# OSSI-1_COMMS.net
KiCad netlist of a schematic drawn in EAGLE
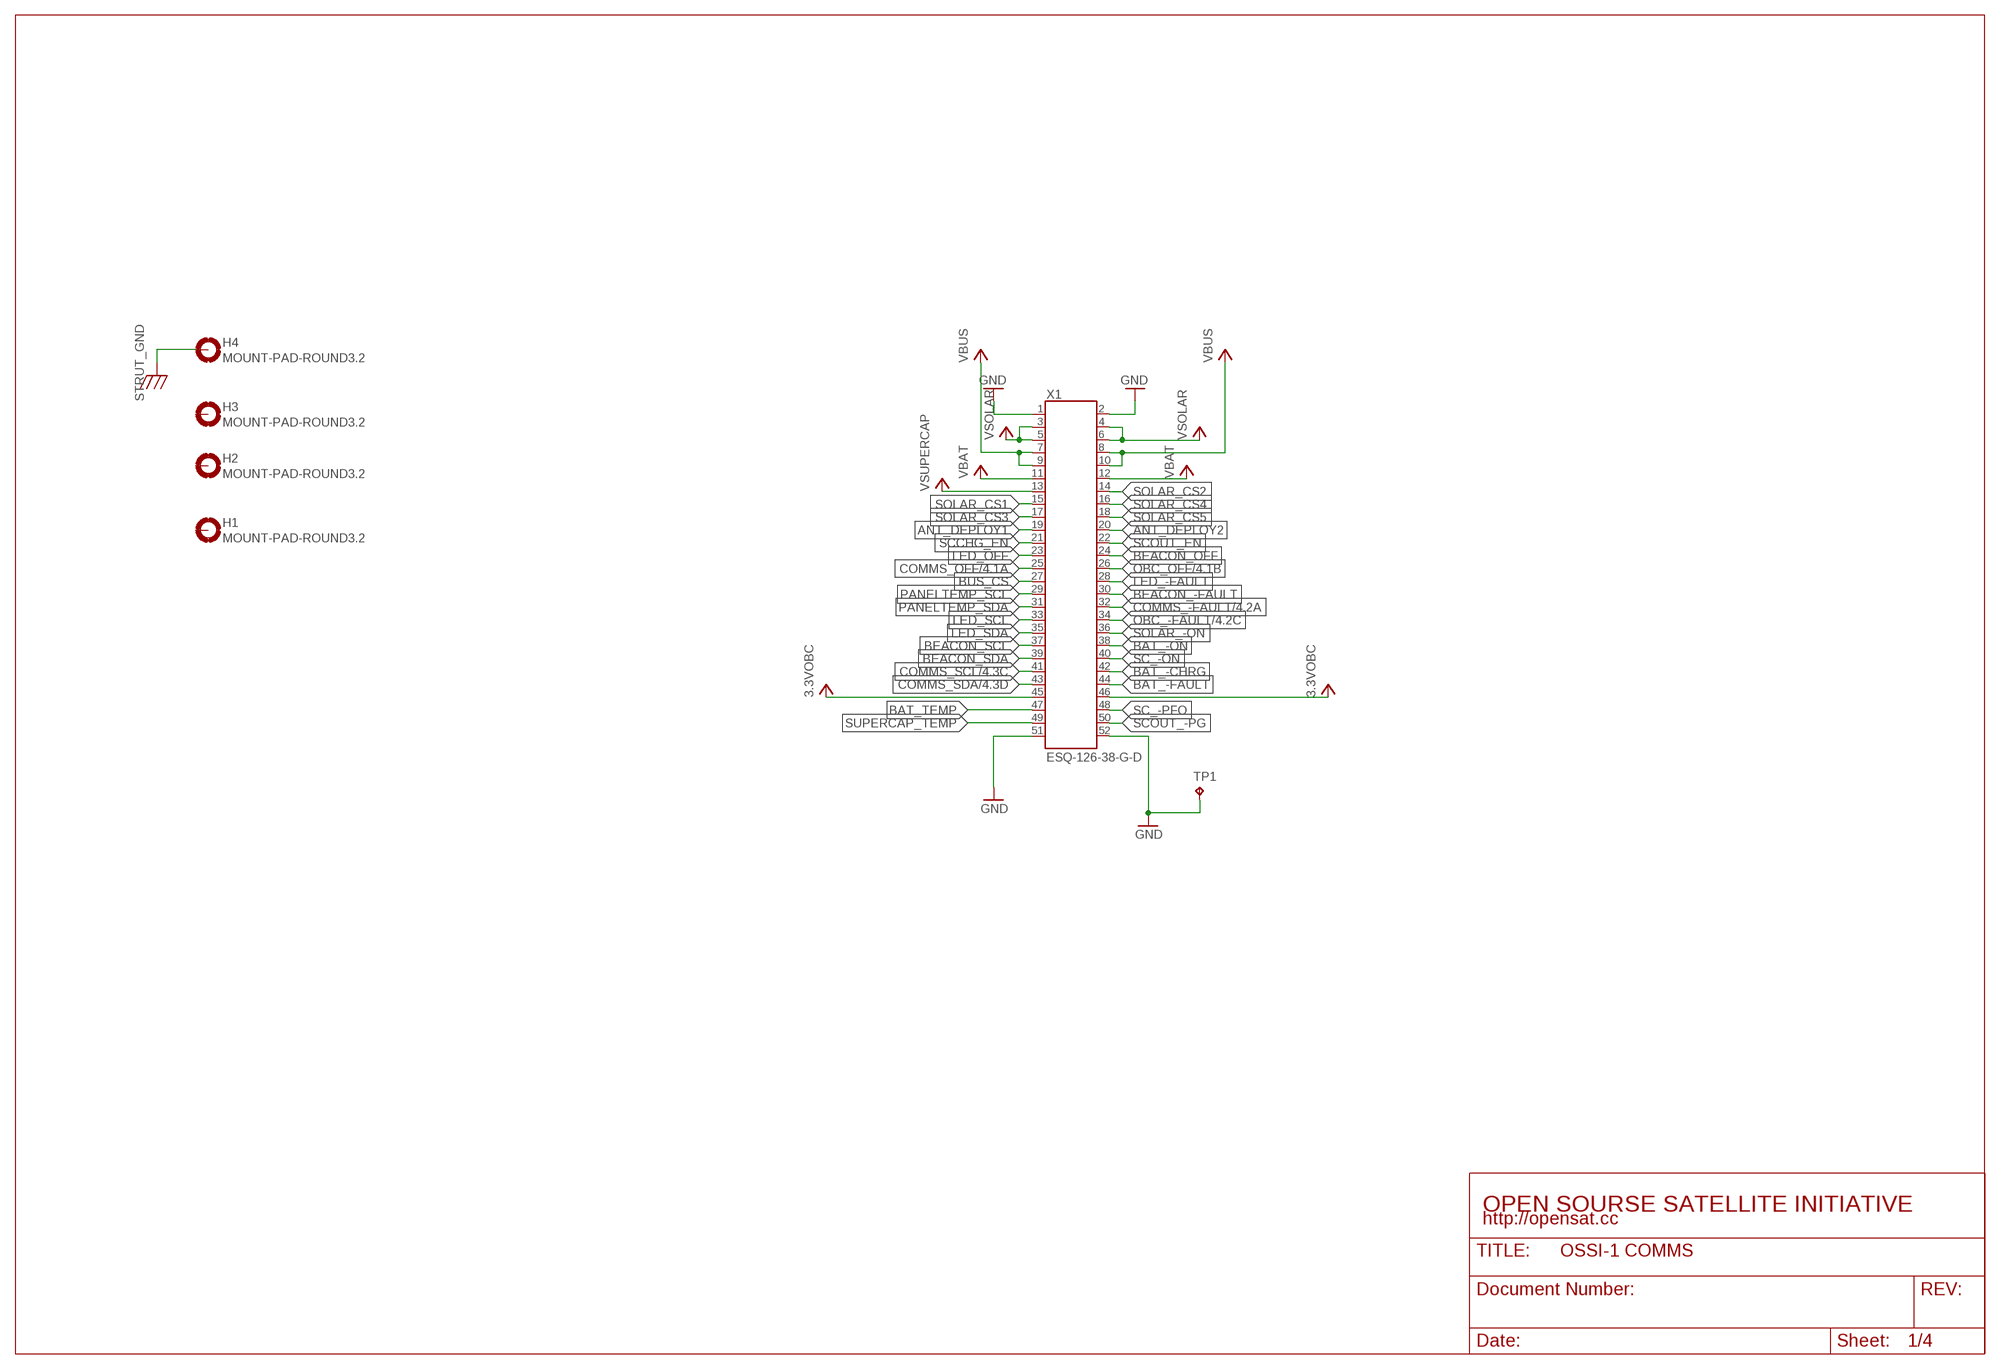
[diagram p0: schematic, sheet 1]
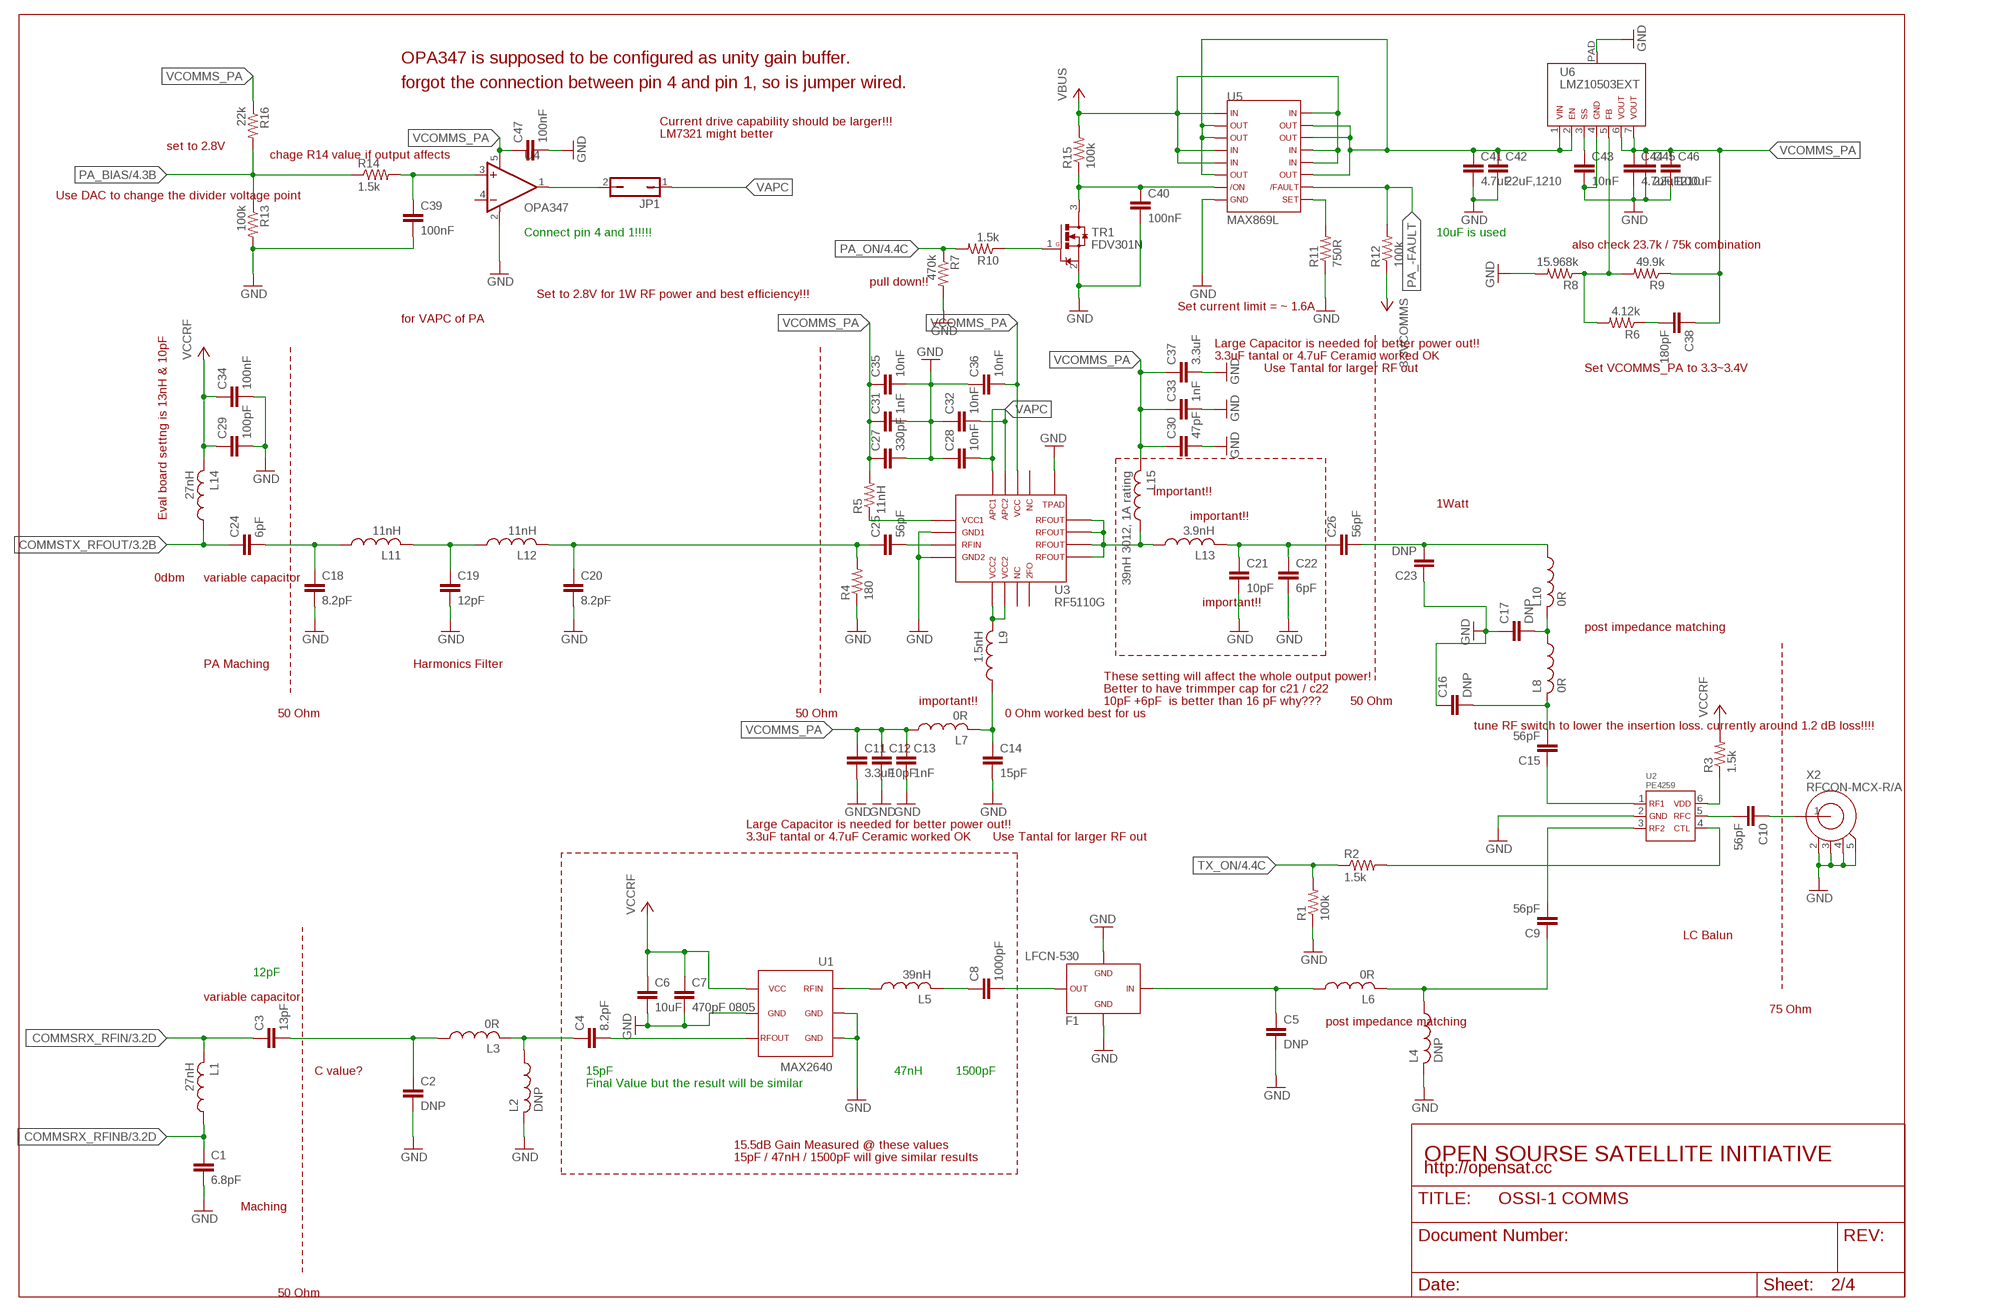
[diagram p1: schematic, sheet 2]
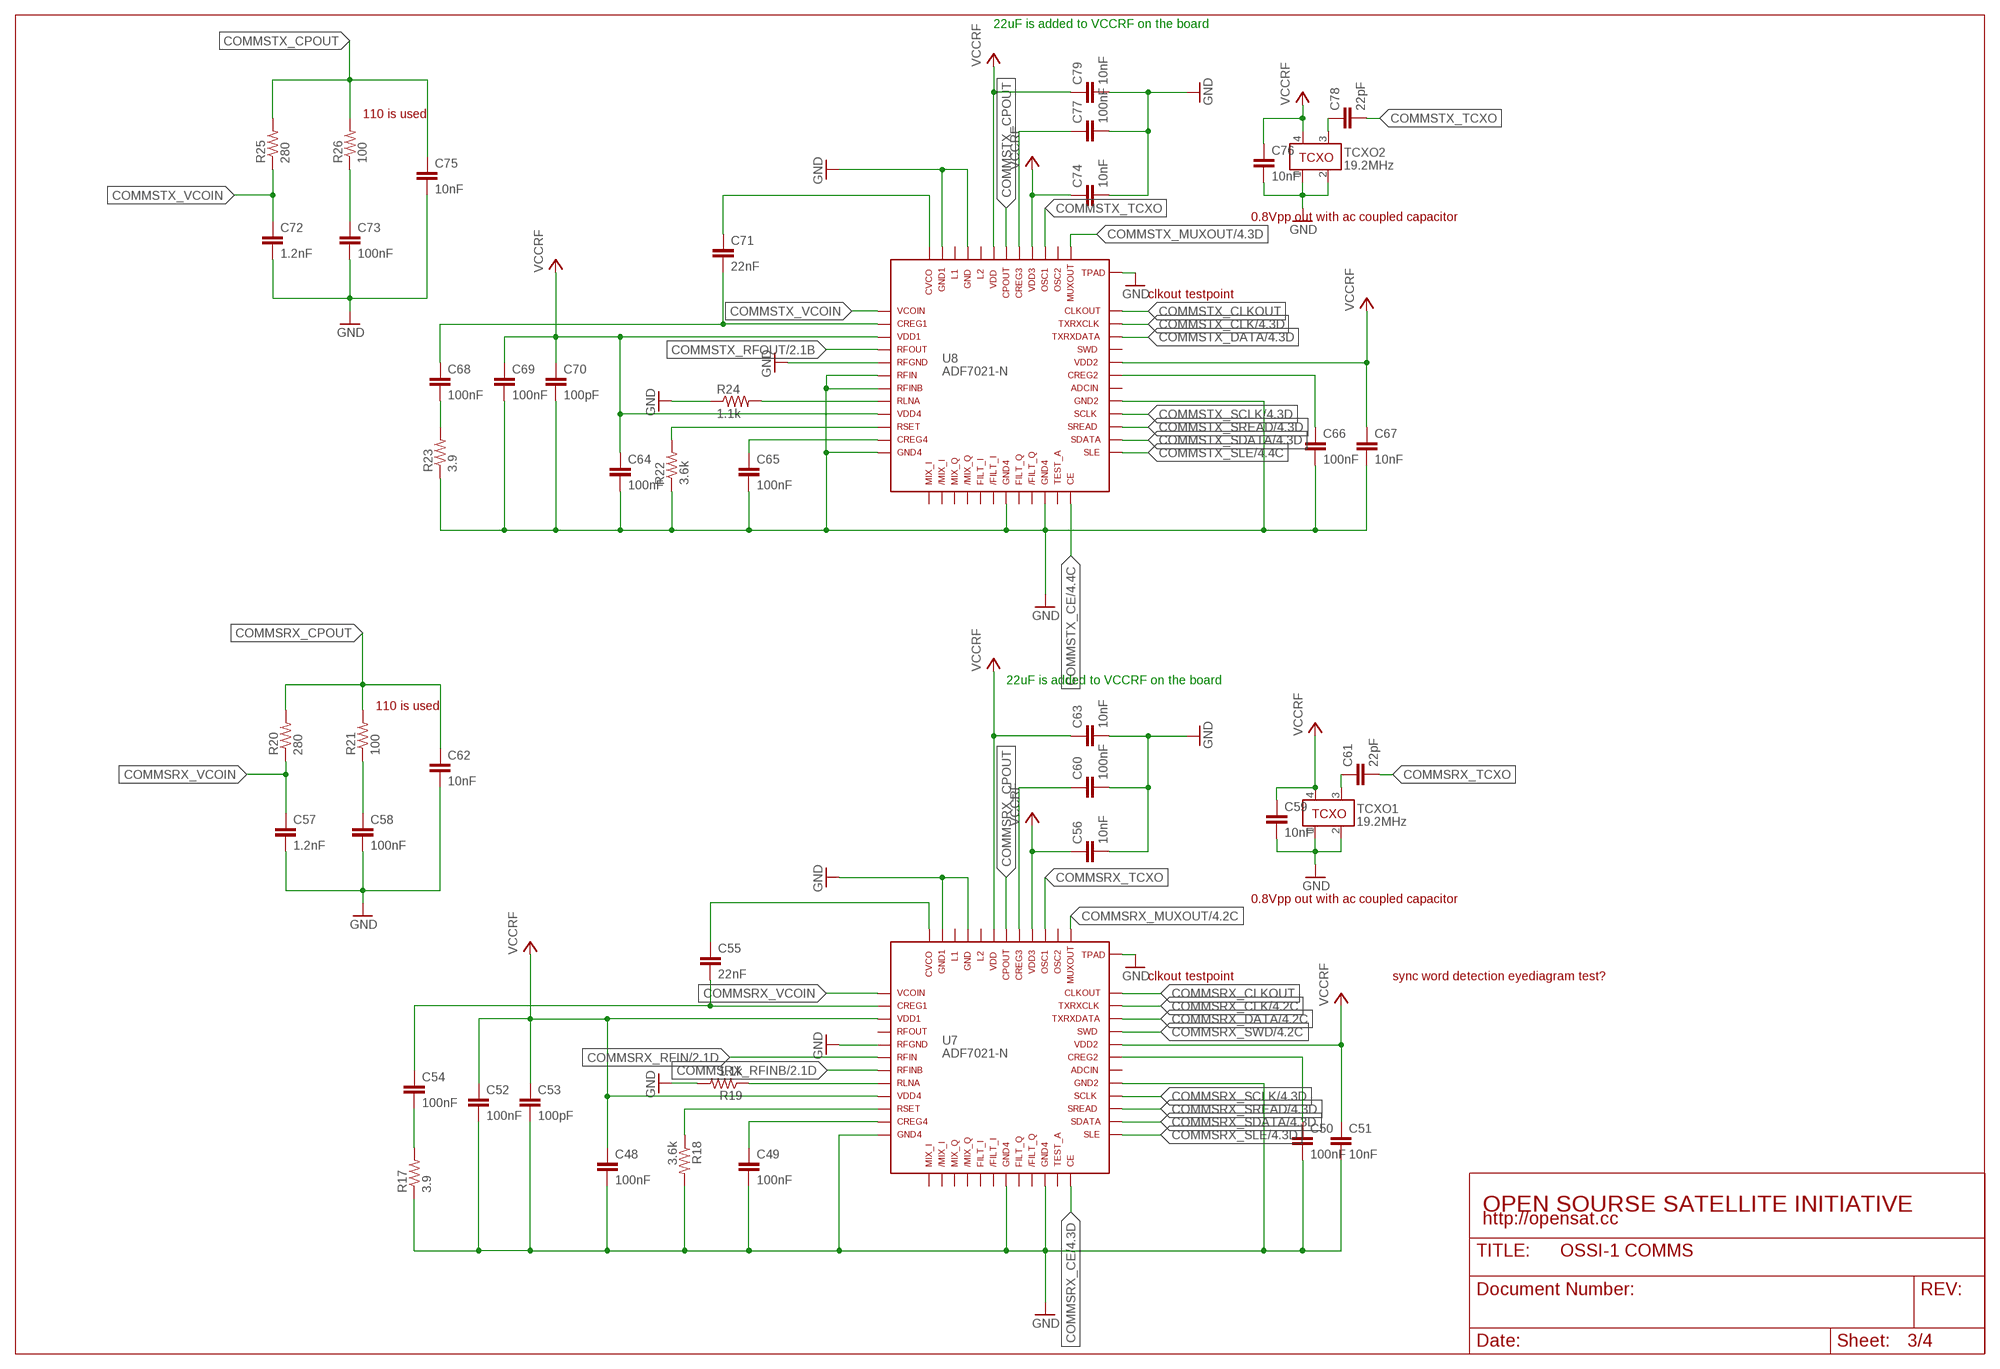
[diagram p2: schematic, sheet 3]
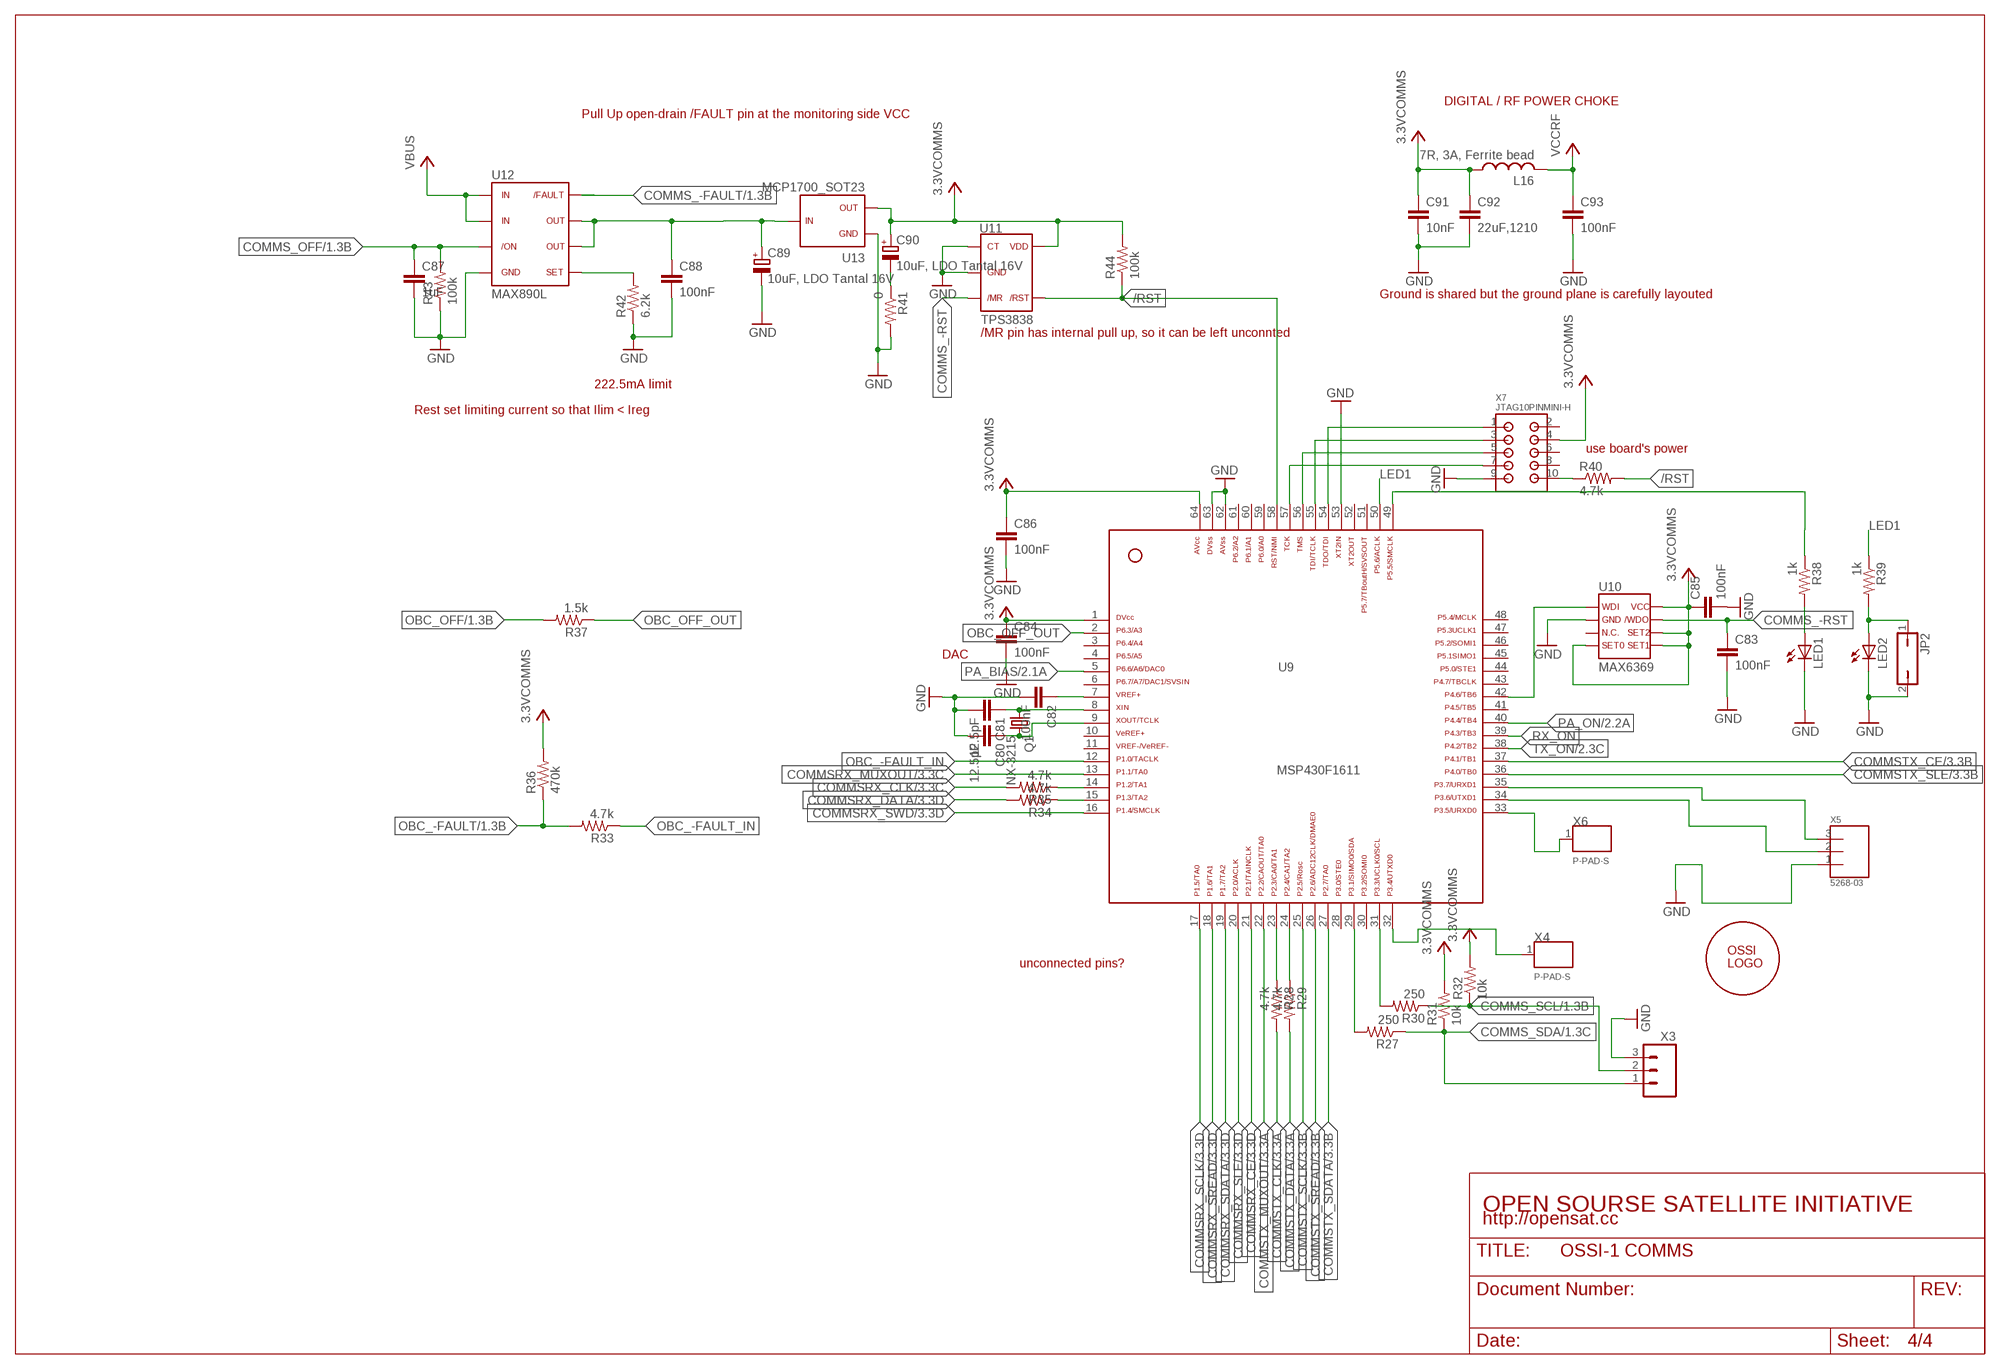
[diagram p3: schematic, sheet 4]

(export (version "E")
  (design (tool "Eeschema 10.0.6"))
  (components
    (comp (ref "H1")
      (value "MOUNT-PAD-ROUND3.2")
      (footprint "eagle-import:3.2-PAD-ROUND")
      (libsource (lib "eagle-import") (part "MOUNT-PAD-ROUND3.2"))
    )
    (comp (ref "H2")
      (value "MOUNT-PAD-ROUND3.2")
      (footprint "eagle-import:3.2-PAD-ROUND")
      (libsource (lib "eagle-import") (part "MOUNT-PAD-ROUND3.2"))
    )
    (comp (ref "H3")
      (value "MOUNT-PAD-ROUND3.2")
      (footprint "eagle-import:3.2-PAD-ROUND")
      (libsource (lib "eagle-import") (part "MOUNT-PAD-ROUND3.2"))
    )
    (comp (ref "H4")
      (value "MOUNT-PAD-ROUND3.2")
      (footprint "eagle-import:3.2-PAD-ROUND")
      (libsource (lib "eagle-import") (part "MOUNT-PAD-ROUND3.2"))
    )
    (comp (ref "TP1")
      (value "TP")
      (footprint "eagle-import:TP-13")
      (libsource (lib "eagle-import") (part "TP"))
    )
    (comp (ref "X1")
      (value "ESQ-126-38-G-D")
      (footprint "eagle-import:ESQ-126-XX-X-D")
      (libsource (lib "eagle-import") (part "ESQ-126-38-G-D"))
    )
    (comp (ref "C1")
      (value "6.8pF")
      (footprint "eagle-import:C0603(1608)")
      (libsource (lib "eagle-import") (part "C0603(1608)"))
    )
    (comp (ref "C2")
      (value "DNP")
      (footprint "eagle-import:C0603(1608)")
      (libsource (lib "eagle-import") (part "C0603(1608)"))
    )
    (comp (ref "C3")
      (value "13pF")
      (footprint "eagle-import:C0603(1608)")
      (libsource (lib "eagle-import") (part "C0603(1608)"))
    )
    (comp (ref "C4")
      (value "8.2pF")
      (footprint "eagle-import:C0603(1608)")
      (libsource (lib "eagle-import") (part "C0603(1608)"))
    )
    (comp (ref "C5")
      (value "DNP")
      (footprint "eagle-import:C0603(1608)")
      (libsource (lib "eagle-import") (part "C0603(1608)"))
    )
    (comp (ref "C6")
      (value "10uF")
      (footprint "eagle-import:C1206-GCM31")
      (libsource (lib "eagle-import") (part "C1206(3216)-GCM31"))
    )
    (comp (ref "C7")
      (value "470pF 0805")
      (footprint "eagle-import:C0805(2012)")
      (libsource (lib "eagle-import") (part "C0805(2012)"))
    )
    (comp (ref "C8")
      (value "1000pF")
      (footprint "eagle-import:C0603(1608)")
      (libsource (lib "eagle-import") (part "C0603(1608)"))
    )
    (comp (ref "C9")
      (value "56pF")
      (footprint "eagle-import:C0603(1608)")
      (libsource (lib "eagle-import") (part "C0603(1608)"))
    )
    (comp (ref "C10")
      (value "56pF")
      (footprint "eagle-import:C0603(1608)")
      (libsource (lib "eagle-import") (part "C0603(1608)"))
    )
    (comp (ref "C11")
      (value "3.3uF")
      (footprint "eagle-import:C1210-TMK325")
      (libsource (lib "eagle-import") (part "C1210(3225)-TMK325"))
    )
    (comp (ref "C12")
      (value "10pF")
      (footprint "eagle-import:C0603(1608)")
      (libsource (lib "eagle-import") (part "C0603(1608)"))
    )
    (comp (ref "C13")
      (value "1nF")
      (footprint "eagle-import:C0603(1608)")
      (libsource (lib "eagle-import") (part "C0603(1608)"))
    )
    (comp (ref "C14")
      (value "15pF")
      (footprint "eagle-import:C0603(1608)")
      (libsource (lib "eagle-import") (part "C0603(1608)"))
    )
    (comp (ref "C15")
      (value "56pF")
      (footprint "eagle-import:C0603(1608)")
      (libsource (lib "eagle-import") (part "C0603(1608)"))
    )
    (comp (ref "C16")
      (value "DNP")
      (footprint "eagle-import:C0603(1608)")
      (libsource (lib "eagle-import") (part "C0603(1608)"))
    )
    (comp (ref "C17")
      (value "DNP")
      (footprint "eagle-import:C0603(1608)")
      (libsource (lib "eagle-import") (part "C0603(1608)"))
    )
    (comp (ref "C18")
      (value "8.2pF")
      (footprint "eagle-import:C0603(1608)")
      (libsource (lib "eagle-import") (part "C0603(1608)"))
    )
    (comp (ref "C19")
      (value "12pF")
      (footprint "eagle-import:C0603(1608)")
      (libsource (lib "eagle-import") (part "C0603(1608)"))
    )
    (comp (ref "C20")
      (value "8.2pF")
      (footprint "eagle-import:C0603(1608)")
      (libsource (lib "eagle-import") (part "C0603(1608)"))
    )
    (comp (ref "C21")
      (value "10pF")
      (footprint "eagle-import:C0603(1608)")
      (libsource (lib "eagle-import") (part "C0603(1608)"))
    )
    (comp (ref "C22")
      (value "6pF")
      (footprint "eagle-import:C0603(1608)")
      (libsource (lib "eagle-import") (part "C0603(1608)"))
    )
    (comp (ref "C23")
      (value "DNP")
      (footprint "eagle-import:C0603(1608)")
      (libsource (lib "eagle-import") (part "C0603(1608)"))
    )
    (comp (ref "C24")
      (value "6pF")
      (footprint "eagle-import:C0603(1608)")
      (libsource (lib "eagle-import") (part "C0603(1608)"))
    )
    (comp (ref "C25")
      (value "56pF")
      (footprint "eagle-import:C0603(1608)")
      (libsource (lib "eagle-import") (part "C0603(1608)"))
    )
    (comp (ref "C26")
      (value "56pF")
      (footprint "eagle-import:C0603(1608)")
      (libsource (lib "eagle-import") (part "C0603(1608)"))
    )
    (comp (ref "C27")
      (value "330pF")
      (footprint "eagle-import:C0603(1608)")
      (libsource (lib "eagle-import") (part "C0603(1608)"))
    )
    (comp (ref "C28")
      (value "10nF")
      (footprint "eagle-import:C0603(1608)")
      (libsource (lib "eagle-import") (part "C0603(1608)"))
    )
    (comp (ref "C29")
      (value "100pF")
      (footprint "eagle-import:C0603(1608)")
      (libsource (lib "eagle-import") (part "C0603(1608)"))
    )
    (comp (ref "C30")
      (value "47pF")
      (footprint "eagle-import:C0603(1608)")
      (libsource (lib "eagle-import") (part "C0603(1608)"))
    )
    (comp (ref "C31")
      (value "1nF")
      (footprint "eagle-import:C0603(1608)")
      (libsource (lib "eagle-import") (part "C0603(1608)"))
    )
    (comp (ref "C32")
      (value "10nF")
      (footprint "eagle-import:C0603(1608)")
      (libsource (lib "eagle-import") (part "C0603(1608)"))
    )
    (comp (ref "C33")
      (value "1nF")
      (footprint "eagle-import:C0603(1608)")
      (libsource (lib "eagle-import") (part "C0603(1608)"))
    )
    (comp (ref "C34")
      (value "100nF")
      (footprint "eagle-import:C0603(1608)")
      (libsource (lib "eagle-import") (part "C0603(1608)"))
    )
    (comp (ref "C35")
      (value "10nF")
      (footprint "eagle-import:C0603(1608)")
      (libsource (lib "eagle-import") (part "C0603(1608)"))
    )
    (comp (ref "C36")
      (value "10nF")
      (footprint "eagle-import:C0603(1608)")
      (libsource (lib "eagle-import") (part "C0603(1608)"))
    )
    (comp (ref "C37")
      (value "3.3uF")
      (footprint "eagle-import:C1210-TMK325")
      (libsource (lib "eagle-import") (part "C1210(3225)-TMK325"))
    )
    (comp (ref "C38")
      (value "180pF")
      (footprint "eagle-import:C0603(1608)")
      (libsource (lib "eagle-import") (part "C0603(1608)"))
    )
    (comp (ref "C39")
      (value "100nF")
      (footprint "eagle-import:C0603(1608)")
      (libsource (lib "eagle-import") (part "C0603(1608)"))
    )
    (comp (ref "C40")
      (value "100nF")
      (footprint "eagle-import:C0603(1608)")
      (libsource (lib "eagle-import") (part "C0603(1608)"))
    )
    (comp (ref "C41")
      (value "4.7uF")
      (footprint "eagle-import:C1210-GCM32")
      (libsource (lib "eagle-import") (part "C1210(3225)-GCM32"))
    )
    (comp (ref "C42")
      (value "22uF,1210")
      (footprint "eagle-import:C1210-GCM32")
      (libsource (lib "eagle-import") (part "C1210(3225)-GCM32"))
    )
    (comp (ref "C43")
      (value "10nF")
      (footprint "eagle-import:C0603(1608)")
      (libsource (lib "eagle-import") (part "C0603(1608)"))
    )
    (comp (ref "C44")
      (value "4.7uF,1210")
      (footprint "eagle-import:C0805(2012)")
      (libsource (lib "eagle-import") (part "C0805(2012)"))
    )
    (comp (ref "C45")
      (value "22uF")
      (footprint "eagle-import:C1210-GCM32")
      (libsource (lib "eagle-import") (part "C1210(3225)-GCM32"))
    )
    (comp (ref "C46")
      (value "100uF")
      (footprint "eagle-import:C1210-GCM32")
      (libsource (lib "eagle-import") (part "C1210(3225)-GCM32"))
    )
    (comp (ref "C47")
      (value "100nF")
      (footprint "eagle-import:C0603(1608)")
      (libsource (lib "eagle-import") (part "C0603(1608)"))
    )
    (comp (ref "F1")
      (value "LFCN-530")
      (footprint "eagle-import:LFCN")
      (libsource (lib "eagle-import") (part "LFCN-160"))
    )
    (comp (ref "JP1")
      (value "JP1Q")
      (footprint "eagle-import:JP1")
      (libsource (lib "eagle-import") (part "JP1Q"))
    )
    (comp (ref "L1")
      (value "27nH")
      (footprint "eagle-import:L0603(1608)")
      (libsource (lib "eagle-import") (part "L0603(1608)"))
    )
    (comp (ref "L2")
      (value "DNP")
      (footprint "eagle-import:L0603(1608)")
      (libsource (lib "eagle-import") (part "L0603(1608)"))
    )
    (comp (ref "L3")
      (value "0R")
      (footprint "eagle-import:L0603(1608)")
      (libsource (lib "eagle-import") (part "L0603(1608)"))
    )
    (comp (ref "L4")
      (value "DNP")
      (footprint "eagle-import:L0603(1608)")
      (libsource (lib "eagle-import") (part "L0603(1608)"))
    )
    (comp (ref "L5")
      (value "39nH")
      (footprint "eagle-import:L0603(1608)")
      (libsource (lib "eagle-import") (part "L0603(1608)"))
    )
    (comp (ref "L6")
      (value "0R")
      (footprint "eagle-import:L0603(1608)")
      (libsource (lib "eagle-import") (part "L0603(1608)"))
    )
    (comp (ref "L7")
      (value "0R")
      (footprint "eagle-import:LQH32CN331K23L")
      (libsource (lib "eagle-import") (part "LLQH32CN"))
    )
    (comp (ref "L8")
      (value "0R")
      (footprint "eagle-import:L0603(1608)")
      (libsource (lib "eagle-import") (part "L0603(1608)"))
    )
    (comp (ref "L9")
      (value "1.5nH")
      (footprint "eagle-import:L0603(1608)")
      (libsource (lib "eagle-import") (part "L0603(1608)"))
    )
    (comp (ref "L10")
      (value "0R")
      (footprint "eagle-import:L0603(1608)")
      (libsource (lib "eagle-import") (part "L0603(1608)"))
    )
    (comp (ref "L11")
      (value "11nH")
      (footprint "eagle-import:L0603(1608)")
      (libsource (lib "eagle-import") (part "L0603(1608)"))
    )
    (comp (ref "L12")
      (value "11nH")
      (footprint "eagle-import:L0603(1608)")
      (libsource (lib "eagle-import") (part "L0603(1608)"))
    )
    (comp (ref "L13")
      (value "3.9nH")
      (footprint "eagle-import:L0603(1608)")
      (libsource (lib "eagle-import") (part "L0603(1608)"))
    )
    (comp (ref "L14")
      (value "27nH")
      (footprint "eagle-import:L0603(1608)")
      (libsource (lib "eagle-import") (part "L0603(1608)"))
    )
    (comp (ref "L15")
      (value "39nH 3012, 1A rating")
      (footprint "eagle-import:NR3012")
      (libsource (lib "eagle-import") (part "LNR3012"))
    )
    (comp (ref "R1")
      (value "100k")
      (footprint "eagle-import:R0603(1608)")
      (libsource (lib "eagle-import") (part "R0603(1608)"))
    )
    (comp (ref "R2")
      (value "1.5k")
      (footprint "eagle-import:R0603(1608)")
      (libsource (lib "eagle-import") (part "R0603(1608)"))
    )
    (comp (ref "R3")
      (value "1.5k")
      (footprint "eagle-import:R0603(1608)")
      (libsource (lib "eagle-import") (part "R0603(1608)"))
    )
    (comp (ref "R4")
      (value "180")
      (footprint "eagle-import:R0603(1608)")
      (libsource (lib "eagle-import") (part "R0603(1608)"))
    )
    (comp (ref "R5")
      (value "11nH")
      (footprint "eagle-import:R0603(1608)")
      (libsource (lib "eagle-import") (part "R0603(1608)"))
    )
    (comp (ref "R6")
      (value "4.12k")
      (footprint "eagle-import:R0603(1608)")
      (libsource (lib "eagle-import") (part "R0603(1608)"))
    )
    (comp (ref "R7")
      (value "470k")
      (footprint "eagle-import:R0603(1608)")
      (libsource (lib "eagle-import") (part "R0603(1608)"))
    )
    (comp (ref "R8")
      (value "15.968k")
      (footprint "eagle-import:R0603(1608)")
      (libsource (lib "eagle-import") (part "R0603(1608)"))
    )
    (comp (ref "R9")
      (value "49.9k")
      (footprint "eagle-import:R0603(1608)")
      (libsource (lib "eagle-import") (part "R0603(1608)"))
    )
    (comp (ref "R10")
      (value "1.5k")
      (footprint "eagle-import:R0603(1608)")
      (libsource (lib "eagle-import") (part "R0603(1608)"))
    )
    (comp (ref "R11")
      (value "750R")
      (footprint "eagle-import:R0603(1608)")
      (libsource (lib "eagle-import") (part "R0603(1608)"))
    )
    (comp (ref "R12")
      (value "100k")
      (footprint "eagle-import:R0603(1608)")
      (libsource (lib "eagle-import") (part "R0603(1608)"))
    )
    (comp (ref "R13")
      (value "100k")
      (footprint "eagle-import:R0603(1608)")
      (libsource (lib "eagle-import") (part "R0603(1608)"))
    )
    (comp (ref "R14")
      (value "1.5k")
      (footprint "eagle-import:R0603(1608)")
      (libsource (lib "eagle-import") (part "R0603(1608)"))
    )
    (comp (ref "R15")
      (value "100k")
      (footprint "eagle-import:R0603(1608)")
      (libsource (lib "eagle-import") (part "R0603(1608)"))
    )
    (comp (ref "R16")
      (value "22k")
      (footprint "eagle-import:R0603(1608)")
      (libsource (lib "eagle-import") (part "R0603(1608)"))
    )
    (comp (ref "TR1")
      (value "FDV301N")
      (footprint "eagle-import:SOT23")
      (libsource (lib "eagle-import") (part "FDV301N"))
    )
    (comp (ref "U1")
      (value "MAX2640")
      (footprint "eagle-import:SOT23-6")
      (libsource (lib "eagle-import") (part "MAX2640"))
    )
    (comp (ref "U2")
      (value "PE4259")
      (footprint "eagle-import:SC70-6")
      (libsource (lib "eagle-import") (part "PE4259"))
    )
    (comp (ref "U3")
      (value "RF5110G")
      (footprint "eagle-import:RF5110G")
      (libsource (lib "eagle-import") (part "RF5110G"))
    )
    (comp (ref "U4")
      (value "OPA347")
      (footprint "eagle-import:SOT23-5DBV")
      (libsource (lib "eagle-import") (part "OPA347"))
    )
    (comp (ref "U5")
      (value "MAX869L")
      (footprint "eagle-import:16QSOP")
      (libsource (lib "eagle-import") (part "MAX869L"))
    )
    (comp (ref "U6")
      (value "LMZ10503EXT")
      (footprint "eagle-import:TO-PMOD-7")
      (libsource (lib "eagle-import") (part "LMZ10503EXT"))
    )
    (comp (ref "X2")
      (value "RFCON-MCX-R/A")
      (footprint "eagle-import:MCX-R_A")
      (libsource (lib "eagle-import") (part "RFCON-MCX-R/A"))
    )
    (comp (ref "C48")
      (value "100nF")
      (footprint "eagle-import:C0603(1608)")
      (libsource (lib "eagle-import") (part "C0603(1608)"))
    )
    (comp (ref "C49")
      (value "100nF")
      (footprint "eagle-import:C0603(1608)")
      (libsource (lib "eagle-import") (part "C0603(1608)"))
    )
    (comp (ref "C50")
      (value "100nF")
      (footprint "eagle-import:C0603(1608)")
      (libsource (lib "eagle-import") (part "C0603(1608)"))
    )
    (comp (ref "C51")
      (value "10nF")
      (footprint "eagle-import:C0603(1608)")
      (libsource (lib "eagle-import") (part "C0603(1608)"))
    )
    (comp (ref "C52")
      (value "100nF")
      (footprint "eagle-import:C0603(1608)")
      (libsource (lib "eagle-import") (part "C0603(1608)"))
    )
    (comp (ref "C53")
      (value "100pF")
      (footprint "eagle-import:C0603(1608)")
      (libsource (lib "eagle-import") (part "C0603(1608)"))
    )
    (comp (ref "C54")
      (value "100nF")
      (footprint "eagle-import:C0603(1608)")
      (libsource (lib "eagle-import") (part "C0603(1608)"))
    )
    (comp (ref "C55")
      (value "22nF")
      (footprint "eagle-import:C0603(1608)")
      (libsource (lib "eagle-import") (part "C0603(1608)"))
    )
    (comp (ref "C56")
      (value "10nF")
      (footprint "eagle-import:C0603(1608)")
      (libsource (lib "eagle-import") (part "C0603(1608)"))
    )
    (comp (ref "C57")
      (value "1.2nF")
      (footprint "eagle-import:C0603(1608)")
      (libsource (lib "eagle-import") (part "C0603(1608)"))
    )
    (comp (ref "C58")
      (value "100nF")
      (footprint "eagle-import:C0603(1608)")
      (libsource (lib "eagle-import") (part "C0603(1608)"))
    )
    (comp (ref "C59")
      (value "10nF")
      (footprint "eagle-import:C0603(1608)")
      (libsource (lib "eagle-import") (part "C0603(1608)"))
    )
    (comp (ref "C60")
      (value "100nF")
      (footprint "eagle-import:C0603(1608)")
      (libsource (lib "eagle-import") (part "C0603(1608)"))
    )
    (comp (ref "C61")
      (value "22pF")
      (footprint "eagle-import:C0603(1608)")
      (libsource (lib "eagle-import") (part "C0603(1608)"))
    )
    (comp (ref "C62")
      (value "10nF")
      (footprint "eagle-import:C0603(1608)")
      (libsource (lib "eagle-import") (part "C0603(1608)"))
    )
    (comp (ref "C63")
      (value "10nF")
      (footprint "eagle-import:C0603(1608)")
      (libsource (lib "eagle-import") (part "C0603(1608)"))
    )
    (comp (ref "C64")
      (value "100nF")
      (footprint "eagle-import:C0603(1608)")
      (libsource (lib "eagle-import") (part "C0603(1608)"))
    )
    (comp (ref "C65")
      (value "100nF")
      (footprint "eagle-import:C0603(1608)")
      (libsource (lib "eagle-import") (part "C0603(1608)"))
    )
    (comp (ref "C66")
      (value "100nF")
      (footprint "eagle-import:C0603(1608)")
      (libsource (lib "eagle-import") (part "C0603(1608)"))
    )
    (comp (ref "C67")
      (value "10nF")
      (footprint "eagle-import:C0603(1608)")
      (libsource (lib "eagle-import") (part "C0603(1608)"))
    )
    (comp (ref "C68")
      (value "100nF")
      (footprint "eagle-import:C0603(1608)")
      (libsource (lib "eagle-import") (part "C0603(1608)"))
    )
    (comp (ref "C69")
      (value "100nF")
      (footprint "eagle-import:C0603(1608)")
      (libsource (lib "eagle-import") (part "C0603(1608)"))
    )
    (comp (ref "C70")
      (value "100pF")
      (footprint "eagle-import:C0603(1608)")
      (libsource (lib "eagle-import") (part "C0603(1608)"))
    )
    (comp (ref "C71")
      (value "22nF")
      (footprint "eagle-import:C0603(1608)")
      (libsource (lib "eagle-import") (part "C0603(1608)"))
    )
    (comp (ref "C72")
      (value "1.2nF")
      (footprint "eagle-import:C0603(1608)")
      (libsource (lib "eagle-import") (part "C0603(1608)"))
    )
    (comp (ref "C73")
      (value "100nF")
      (footprint "eagle-import:C0603(1608)")
      (libsource (lib "eagle-import") (part "C0603(1608)"))
    )
    (comp (ref "C74")
      (value "10nF")
      (footprint "eagle-import:C0603(1608)")
      (libsource (lib "eagle-import") (part "C0603(1608)"))
    )
    (comp (ref "C75")
      (value "10nF")
      (footprint "eagle-import:C0603(1608)")
      (libsource (lib "eagle-import") (part "C0603(1608)"))
    )
    (comp (ref "C76")
      (value "10nF")
      (footprint "eagle-import:C0603(1608)")
      (libsource (lib "eagle-import") (part "C0603(1608)"))
    )
    (comp (ref "C77")
      (value "100nF")
      (footprint "eagle-import:C0603(1608)")
      (libsource (lib "eagle-import") (part "C0603(1608)"))
    )
    (comp (ref "C78")
      (value "22pF")
      (footprint "eagle-import:C0603(1608)")
      (libsource (lib "eagle-import") (part "C0603(1608)"))
    )
    (comp (ref "C79")
      (value "10nF")
      (footprint "eagle-import:C0603(1608)")
      (libsource (lib "eagle-import") (part "C0603(1608)"))
    )
    (comp (ref "R17")
      (value "3.9")
      (footprint "eagle-import:R0603(1608)")
      (libsource (lib "eagle-import") (part "R0603(1608)"))
    )
    (comp (ref "R18")
      (value "3.6k")
      (footprint "eagle-import:R0603(1608)")
      (libsource (lib "eagle-import") (part "R0603(1608)"))
    )
    (comp (ref "R19")
      (value "1.1k")
      (footprint "eagle-import:R0603(1608)")
      (libsource (lib "eagle-import") (part "R0603(1608)"))
    )
    (comp (ref "R20")
      (value "280")
      (footprint "eagle-import:R0603(1608)")
      (libsource (lib "eagle-import") (part "R0603(1608)"))
    )
    (comp (ref "R21")
      (value "100")
      (footprint "eagle-import:R0603(1608)")
      (libsource (lib "eagle-import") (part "R0603(1608)"))
    )
    (comp (ref "R22")
      (value "3.6k")
      (footprint "eagle-import:R0603(1608)")
      (libsource (lib "eagle-import") (part "R0603(1608)"))
    )
    (comp (ref "R23")
      (value "3.9")
      (footprint "eagle-import:R0603(1608)")
      (libsource (lib "eagle-import") (part "R0603(1608)"))
    )
    (comp (ref "R24")
      (value "1.1k")
      (footprint "eagle-import:R0603(1608)")
      (libsource (lib "eagle-import") (part "R0603(1608)"))
    )
    (comp (ref "R25")
      (value "280")
      (footprint "eagle-import:R0603(1608)")
      (libsource (lib "eagle-import") (part "R0603(1608)"))
    )
    (comp (ref "R26")
      (value "100")
      (footprint "eagle-import:R0603(1608)")
      (libsource (lib "eagle-import") (part "R0603(1608)"))
    )
    (comp (ref "TCXO1")
      (value "19.2MHz")
      (footprint "eagle-import:TCXO_M532")
      (libsource (lib "eagle-import") (part "TCXO-M532"))
    )
    (comp (ref "TCXO2")
      (value "19.2MHz")
      (footprint "eagle-import:TCXO_M532")
      (libsource (lib "eagle-import") (part "TCXO-M532"))
    )
    (comp (ref "U7")
      (value "ADF7021-N")
      (footprint "eagle-import:LFCSP48")
      (libsource (lib "eagle-import") (part "ADF7021-N"))
    )
    (comp (ref "U8")
      (value "ADF7021-N")
      (footprint "eagle-import:LFCSP48")
      (libsource (lib "eagle-import") (part "ADF7021-N"))
    )
    (comp (ref "C80")
      (value "12.5pF")
      (footprint "eagle-import:C0603(1608)")
      (libsource (lib "eagle-import") (part "C0603(1608)"))
    )
    (comp (ref "C81")
      (value "12.5pF")
      (footprint "eagle-import:C0603(1608)")
      (libsource (lib "eagle-import") (part "C0603(1608)"))
    )
    (comp (ref "C82")
      (value "100nF")
      (footprint "eagle-import:C0603(1608)")
      (libsource (lib "eagle-import") (part "C0603(1608)"))
    )
    (comp (ref "C83")
      (value "100nF")
      (footprint "eagle-import:C0603(1608)")
      (libsource (lib "eagle-import") (part "C0603(1608)"))
    )
    (comp (ref "C84")
      (value "100nF")
      (footprint "eagle-import:C0603(1608)")
      (libsource (lib "eagle-import") (part "C0603(1608)"))
    )
    (comp (ref "C85")
      (value "100nF")
      (footprint "eagle-import:C0603(1608)")
      (libsource (lib "eagle-import") (part "C0603(1608)"))
    )
    (comp (ref "C86")
      (value "100nF")
      (footprint "eagle-import:C0603(1608)")
      (libsource (lib "eagle-import") (part "C0603(1608)"))
    )
    (comp (ref "C87")
      (value "1uF")
      (footprint "eagle-import:C0603(1608)")
      (libsource (lib "eagle-import") (part "C0603(1608)"))
    )
    (comp (ref "C88")
      (value "100nF")
      (footprint "eagle-import:C0603(1608)")
      (libsource (lib "eagle-import") (part "C0603(1608)"))
    )
    (comp (ref "C89")
      (value "10uF, LDO Tantal 16V")
      (footprint "eagle-import:C1206(3216)-A")
      (libsource (lib "eagle-import") (part "C-TANTAL-A"))
    )
    (comp (ref "C90")
      (value "10uF, LDO Tantal 16V")
      (footprint "eagle-import:C1206(3216)-A")
      (libsource (lib "eagle-import") (part "C-TANTAL-A"))
    )
    (comp (ref "C91")
      (value "10nF")
      (footprint "eagle-import:C0603(1608)")
      (libsource (lib "eagle-import") (part "C0603(1608)"))
    )
    (comp (ref "C92")
      (value "22uF,1210")
      (footprint "eagle-import:C1210-GCM32")
      (libsource (lib "eagle-import") (part "C1210(3225)-GCM32"))
    )
    (comp (ref "C93")
      (value "100nF")
      (footprint "eagle-import:C0603(1608)")
      (libsource (lib "eagle-import") (part "C0603(1608)"))
    )
    (comp (ref "JP2")
      (value "JP1Q")
      (footprint "eagle-import:JP1")
      (libsource (lib "eagle-import") (part "JP1Q"))
    )
    (comp (ref "L16")
      (value "7R, 3A, Ferrite bead")
      (footprint "eagle-import:L0805(2012)")
      (libsource (lib "eagle-import") (part "L0805(2012)"))
    )
    (comp (ref "LED1")
      (value "LEDCHIPLED_0603")
      (footprint "eagle-import:CHIPLED_0603")
      (libsource (lib "eagle-import") (part "LEDCHIPLED_0603"))
    )
    (comp (ref "LED2")
      (value "LEDCHIPLED_0603")
      (footprint "eagle-import:CHIPLED_0603")
      (libsource (lib "eagle-import") (part "LEDCHIPLED_0603"))
    )
    (comp (ref "Q1")
      (value "NX-3215")
      (footprint "eagle-import:NX-3215")
      (libsource (lib "eagle-import") (part "NX-3215"))
    )
    (comp (ref "R27")
      (value "250")
      (footprint "eagle-import:R0603(1608)")
      (libsource (lib "eagle-import") (part "R0603(1608)"))
    )
    (comp (ref "R28")
      (value "4.7k")
      (footprint "eagle-import:R0603(1608)")
      (libsource (lib "eagle-import") (part "R0603(1608)"))
    )
    (comp (ref "R29")
      (value "4.7k")
      (footprint "eagle-import:R0603(1608)")
      (libsource (lib "eagle-import") (part "R0603(1608)"))
    )
    (comp (ref "R30")
      (value "250")
      (footprint "eagle-import:R0603(1608)")
      (libsource (lib "eagle-import") (part "R0603(1608)"))
    )
    (comp (ref "R31")
      (value "10k")
      (footprint "eagle-import:R0603(1608)")
      (libsource (lib "eagle-import") (part "R0603(1608)"))
    )
    (comp (ref "R32")
      (value "10k")
      (footprint "eagle-import:R0603(1608)")
      (libsource (lib "eagle-import") (part "R0603(1608)"))
    )
    (comp (ref "R33")
      (value "4.7k")
      (footprint "eagle-import:R0603(1608)")
      (libsource (lib "eagle-import") (part "R0603(1608)"))
    )
    (comp (ref "R34")
      (value "4.7k")
      (footprint "eagle-import:R0603(1608)")
      (libsource (lib "eagle-import") (part "R0603(1608)"))
    )
    (comp (ref "R35")
      (value "4.7k")
      (footprint "eagle-import:R0603(1608)")
      (libsource (lib "eagle-import") (part "R0603(1608)"))
    )
    (comp (ref "R36")
      (value "470k")
      (footprint "eagle-import:R0603(1608)")
      (libsource (lib "eagle-import") (part "R0603(1608)"))
    )
    (comp (ref "R37")
      (value "1.5k")
      (footprint "eagle-import:R0603(1608)")
      (libsource (lib "eagle-import") (part "R0603(1608)"))
    )
    (comp (ref "R38")
      (value "1k")
      (footprint "eagle-import:R0603(1608)")
      (libsource (lib "eagle-import") (part "R0603(1608)"))
    )
    (comp (ref "R39")
      (value "1k")
      (footprint "eagle-import:R0603(1608)")
      (libsource (lib "eagle-import") (part "R0603(1608)"))
    )
    (comp (ref "R40")
      (value "4.7k")
      (footprint "eagle-import:R0603(1608)")
      (libsource (lib "eagle-import") (part "R0603(1608)"))
    )
    (comp (ref "R41")
      (value "0")
      (footprint "eagle-import:R0603(1608)")
      (libsource (lib "eagle-import") (part "R0603(1608)"))
    )
    (comp (ref "R42")
      (value "6.2k")
      (footprint "eagle-import:R0603(1608)")
      (libsource (lib "eagle-import") (part "R0603(1608)"))
    )
    (comp (ref "R43")
      (value "100k")
      (footprint "eagle-import:R0603(1608)")
      (libsource (lib "eagle-import") (part "R0603(1608)"))
    )
    (comp (ref "R44")
      (value "100k")
      (footprint "eagle-import:R0603(1608)")
      (libsource (lib "eagle-import") (part "R0603(1608)"))
    )
    (comp (ref "U$1")
      (value "OSSILOGORECT")
      (footprint "eagle-import:OSSILOGORECT1005")
      (libsource (lib "eagle-import") (part "OSSILOGORECT"))
    )
    (comp (ref "U9")
      (value "MSP430F1611")
      (footprint "eagle-import:PM_PAG64")
      (libsource (lib "eagle-import") (part "MSP430F1611"))
    )
    (comp (ref "U10")
      (value "MAX6369")
      (footprint "eagle-import:SOT23-8")
      (libsource (lib "eagle-import") (part "MAX6369"))
    )
    (comp (ref "U11")
      (value "TPS3838")
      (footprint "eagle-import:SOT23-5DBV")
      (libsource (lib "eagle-import") (part "TPS3838"))
    )
    (comp (ref "U12")
      (value "MAX890L")
      (footprint "eagle-import:SO8")
      (libsource (lib "eagle-import") (part "MAX890L"))
    )
    (comp (ref "U13")
      (value "MCP1700_SOT23")
      (footprint "eagle-import:SOT23")
      (libsource (lib "eagle-import") (part "MCP1700_SOT23"))
    )
    (comp (ref "X3")
      (value "M03PTH")
      (footprint "eagle-import:1X03")
      (libsource (lib "eagle-import") (part "M03PTH"))
    )
    (comp (ref "X4")
      (value "P-PAD-S")
      (footprint "eagle-import:P-PAD-S")
      (libsource (lib "eagle-import") (part "P-PAD-S"))
    )
    (comp (ref "X5")
      (value "5268-03")
      (footprint "eagle-import:5268-03")
      (libsource (lib "eagle-import") (part "5268-03"))
    )
    (comp (ref "X6")
      (value "P-PAD-S")
      (footprint "eagle-import:P-PAD-S")
      (libsource (lib "eagle-import") (part "P-PAD-S"))
    )
    (comp (ref "X7")
      (value "JTAG10PINMINI-H")
      (footprint "eagle-import:M50-3200545")
      (libsource (lib "eagle-import") (part "JTAG10PINMINI-H"))
    )
  )
  (nets
    (net (code "1") (name "3.3VCOMMS") (class "Default")
      (node (ref "C84") (pin "1") (pinfunction "1_1") (pintype "passive"))
      (node (ref "C85") (pin "1") (pinfunction "1_1") (pintype "passive"))
      (node (ref "C86") (pin "1") (pinfunction "1_1") (pintype "passive"))
      (node (ref "C90") (pin "1") (pinfunction "+_1") (pintype "passive"))
      (node (ref "C91") (pin "1") (pinfunction "1_1") (pintype "passive"))
      (node (ref "C92") (pin "P$1") (pinfunction "1_P$1") (pintype "passive"))
      (node (ref "L16") (pin "1") (pinfunction "1_1") (pintype "passive"))
      (node (ref "R12") (pin "1") (pinfunction "1_1") (pintype "passive"))
      (node (ref "R31") (pin "2") (pinfunction "2_2") (pintype "passive"))
      (node (ref "R32") (pin "2") (pinfunction "2_2") (pintype "passive"))
      (node (ref "R36") (pin "2") (pinfunction "2_2") (pintype "passive"))
      (node (ref "R44") (pin "2") (pinfunction "2_2") (pintype "passive"))
      (node (ref "U10") (pin "4") (pinfunction "P$4_4") (pintype "passive"))
      (node (ref "U10") (pin "5") (pinfunction "P$5_5") (pintype "passive"))
      (node (ref "U10") (pin "6") (pinfunction "P$6_6") (pintype "passive"))
      (node (ref "U10") (pin "8") (pinfunction "P$8_8") (pintype "power_in"))
      (node (ref "U11") (pin "5") (pinfunction "P$5_5") (pintype "power_in"))
      (node (ref "U13") (pin "2") (pinfunction "2_2") (pintype "power_in"))
      (node (ref "U9") (pin "1") (pinfunction "1_1") (pintype "power_in"))
      (node (ref "U9") (pin "64") (pinfunction "64_64") (pintype "power_in"))
      (node (ref "X7") (pin "4") (pinfunction "4_4") (pintype "bidirectional"))
    )
    (net (code "2") (name "3.3VOBC") (class "Default")
      (node (ref "X1") (pin "45") (pinfunction "45_45") (pintype "bidirectional"))
      (node (ref "X1") (pin "46") (pinfunction "46_46") (pintype "bidirectional"))
    )
    (net (code "3") (name "ANT_DEPLOY1") (class "Default")
      (node (ref "X1") (pin "19") (pinfunction "19_19") (pintype "bidirectional"))
    )
    (net (code "4") (name "ANT_DEPLOY2") (class "Default")
      (node (ref "X1") (pin "20") (pinfunction "20_20") (pintype "bidirectional"))
    )
    (net (code "5") (name "BAT_-CHRG") (class "Default")
      (node (ref "X1") (pin "42") (pinfunction "42_42") (pintype "bidirectional"))
    )
    (net (code "6") (name "BAT_-FAULT") (class "Default")
      (node (ref "X1") (pin "44") (pinfunction "44_44") (pintype "bidirectional"))
    )
    (net (code "7") (name "BAT_-ON") (class "Default")
      (node (ref "X1") (pin "38") (pinfunction "38_38") (pintype "bidirectional"))
    )
    (net (code "8") (name "BAT_TEMP") (class "Default")
      (node (ref "X1") (pin "47") (pinfunction "47_47") (pintype "bidirectional"))
    )
    (net (code "9") (name "BEACON_-FAULT") (class "Default")
      (node (ref "X1") (pin "30") (pinfunction "30_30") (pintype "bidirectional"))
    )
    (net (code "10") (name "BEACON_OFF") (class "Default")
      (node (ref "X1") (pin "24") (pinfunction "24_24") (pintype "bidirectional"))
    )
    (net (code "11") (name "BEACON_SCL") (class "Default")
      (node (ref "X1") (pin "37") (pinfunction "37_37") (pintype "bidirectional"))
    )
    (net (code "12") (name "BEACON_SDA") (class "Default")
      (node (ref "X1") (pin "39") (pinfunction "39_39") (pintype "bidirectional"))
    )
    (net (code "13") (name "BUS_CS") (class "Default")
      (node (ref "X1") (pin "27") (pinfunction "27_27") (pintype "bidirectional"))
    )
    (net (code "14") (name "COMMSRX_CE") (class "Default")
      (node (ref "U7") (pin "24") (pinfunction "P$24_24") (pintype "bidirectional"))
      (node (ref "U9") (pin "21") (pinfunction "21_21") (pintype "bidirectional"))
    )
    (net (code "15") (name "COMMSRX_CLK") (class "Default")
      (node (ref "R35") (pin "2") (pinfunction "2_2") (pintype "passive"))
      (node (ref "U7") (pin "35") (pinfunction "P$35_35") (pintype "bidirectional"))
    )
    (net (code "16") (name "COMMSRX_CLKOUT") (class "Default")
      (node (ref "U7") (pin "36") (pinfunction "P$36_36") (pintype "bidirectional"))
    )
    (net (code "17") (name "COMMSRX_CPOUT") (class "Default")
      (node (ref "C62") (pin "1") (pinfunction "1_1") (pintype "passive"))
      (node (ref "R20") (pin "2") (pinfunction "2_2") (pintype "passive"))
      (node (ref "R21") (pin "2") (pinfunction "2_2") (pintype "passive"))
      (node (ref "U7") (pin "42") (pinfunction "P$42_42") (pintype "bidirectional"))
    )
    (net (code "18") (name "COMMSRX_DATA") (class "Default")
      (node (ref "R34") (pin "2") (pinfunction "2_2") (pintype "passive"))
      (node (ref "U7") (pin "34") (pinfunction "P$34_34") (pintype "bidirectional"))
    )
    (net (code "19") (name "COMMSRX_MUXOUT") (class "Default")
      (node (ref "U7") (pin "37") (pinfunction "P$37_37") (pintype "bidirectional"))
      (node (ref "U9") (pin "13") (pinfunction "13_13") (pintype "bidirectional"))
    )
    (net (code "20") (name "COMMSRX_RFIN") (class "Default")
      (node (ref "C3") (pin "1") (pinfunction "1_1") (pintype "passive"))
      (node (ref "L1") (pin "2") (pinfunction "2_2") (pintype "passive"))
      (node (ref "U7") (pin "6") (pinfunction "P$6_6") (pintype "bidirectional"))
    )
    (net (code "21") (name "COMMSRX_RFINB") (class "Default")
      (node (ref "C1") (pin "1") (pinfunction "1_1") (pintype "passive"))
      (node (ref "L1") (pin "1") (pinfunction "1_1") (pintype "passive"))
      (node (ref "U7") (pin "7") (pinfunction "P$7_7") (pintype "bidirectional"))
    )
    (net (code "22") (name "COMMSRX_SCLK") (class "Default")
      (node (ref "U7") (pin "28") (pinfunction "P$28_28") (pintype "bidirectional"))
      (node (ref "U9") (pin "17") (pinfunction "17_17") (pintype "bidirectional"))
    )
    (net (code "23") (name "COMMSRX_SDATA") (class "Default")
      (node (ref "U7") (pin "26") (pinfunction "P$26_26") (pintype "bidirectional"))
      (node (ref "U9") (pin "19") (pinfunction "19_19") (pintype "bidirectional"))
    )
    (net (code "24") (name "COMMSRX_SLE") (class "Default")
      (node (ref "U7") (pin "25") (pinfunction "P$25_25") (pintype "bidirectional"))
      (node (ref "U9") (pin "20") (pinfunction "20_20") (pintype "bidirectional"))
    )
    (net (code "25") (name "COMMSRX_SREAD") (class "Default")
      (node (ref "U7") (pin "27") (pinfunction "P$27_27") (pintype "bidirectional"))
      (node (ref "U9") (pin "18") (pinfunction "18_18") (pintype "bidirectional"))
    )
    (net (code "26") (name "COMMSRX_SWD") (class "Default")
      (node (ref "U7") (pin "33") (pinfunction "P$33_33") (pintype "bidirectional"))
      (node (ref "U9") (pin "16") (pinfunction "16_16") (pintype "bidirectional"))
    )
    (net (code "27") (name "COMMSRX_TCXO") (class "Default")
      (node (ref "C61") (pin "2") (pinfunction "2_2") (pintype "passive"))
      (node (ref "U7") (pin "39") (pinfunction "P$39_39") (pintype "bidirectional"))
    )
    (net (code "28") (name "COMMSRX_VCOIN") (class "Default")
      (node (ref "C57") (pin "1") (pinfunction "1_1") (pintype "passive"))
      (node (ref "R20") (pin "1") (pinfunction "1_1") (pintype "passive"))
      (node (ref "U7") (pin "1") (pinfunction "P$1_1") (pintype "bidirectional"))
    )
    (net (code "29") (name "COMMSTX_CE") (class "Default")
      (node (ref "U8") (pin "24") (pinfunction "P$24_24") (pintype "bidirectional"))
      (node (ref "U9") (pin "37") (pinfunction "37_37") (pintype "bidirectional"))
    )
    (net (code "30") (name "COMMSTX_CLK") (class "Default")
      (node (ref "R28") (pin "2") (pinfunction "2_2") (pintype "passive"))
      (node (ref "U8") (pin "35") (pinfunction "P$35_35") (pintype "bidirectional"))
    )
    (net (code "31") (name "COMMSTX_CLKOUT") (class "Default")
      (node (ref "U8") (pin "36") (pinfunction "P$36_36") (pintype "bidirectional"))
    )
    (net (code "32") (name "COMMSTX_CPOUT") (class "Default")
      (node (ref "C75") (pin "1") (pinfunction "1_1") (pintype "passive"))
      (node (ref "R25") (pin "2") (pinfunction "2_2") (pintype "passive"))
      (node (ref "R26") (pin "2") (pinfunction "2_2") (pintype "passive"))
      (node (ref "U8") (pin "42") (pinfunction "P$42_42") (pintype "bidirectional"))
    )
    (net (code "33") (name "COMMSTX_DATA") (class "Default")
      (node (ref "R29") (pin "2") (pinfunction "2_2") (pintype "passive"))
      (node (ref "U8") (pin "34") (pinfunction "P$34_34") (pintype "bidirectional"))
    )
    (net (code "34") (name "COMMSTX_MUXOUT") (class "Default")
      (node (ref "U8") (pin "37") (pinfunction "P$37_37") (pintype "bidirectional"))
      (node (ref "U9") (pin "22") (pinfunction "22_22") (pintype "bidirectional"))
    )
    (net (code "35") (name "COMMSTX_RFOUT") (class "Default")
      (node (ref "C24") (pin "1") (pinfunction "1_1") (pintype "passive"))
      (node (ref "L14") (pin "1") (pinfunction "1_1") (pintype "passive"))
      (node (ref "U8") (pin "4") (pinfunction "P$4_4") (pintype "bidirectional"))
    )
    (net (code "36") (name "COMMSTX_SCLK") (class "Default")
      (node (ref "U8") (pin "28") (pinfunction "P$28_28") (pintype "bidirectional"))
      (node (ref "U9") (pin "25") (pinfunction "25_25") (pintype "bidirectional"))
    )
    (net (code "37") (name "COMMSTX_SDATA") (class "Default")
      (node (ref "U8") (pin "26") (pinfunction "P$26_26") (pintype "bidirectional"))
      (node (ref "U9") (pin "27") (pinfunction "27_27") (pintype "bidirectional"))
    )
    (net (code "38") (name "COMMSTX_SLE") (class "Default")
      (node (ref "U8") (pin "25") (pinfunction "P$25_25") (pintype "bidirectional"))
      (node (ref "U9") (pin "36") (pinfunction "36_36") (pintype "output"))
    )
    (net (code "39") (name "COMMSTX_SREAD") (class "Default")
      (node (ref "U8") (pin "27") (pinfunction "P$27_27") (pintype "bidirectional"))
      (node (ref "U9") (pin "26") (pinfunction "26_26") (pintype "bidirectional"))
    )
    (net (code "40") (name "COMMSTX_TCXO") (class "Default")
      (node (ref "C78") (pin "2") (pinfunction "2_2") (pintype "passive"))
      (node (ref "U8") (pin "39") (pinfunction "P$39_39") (pintype "bidirectional"))
    )
    (net (code "41") (name "COMMSTX_VCOIN") (class "Default")
      (node (ref "C72") (pin "1") (pinfunction "1_1") (pintype "passive"))
      (node (ref "R25") (pin "1") (pinfunction "1_1") (pintype "passive"))
      (node (ref "U8") (pin "1") (pinfunction "P$1_1") (pintype "bidirectional"))
    )
    (net (code "42") (name "COMMS_-FAULT") (class "Default")
      (node (ref "U12") (pin "8") (pinfunction "P$8_8") (pintype "output"))
      (node (ref "X1") (pin "32") (pinfunction "32_32") (pintype "bidirectional"))
    )
    (net (code "43") (name "COMMS_-RST") (class "Default")
      (node (ref "C83") (pin "1") (pinfunction "1_1") (pintype "passive"))
      (node (ref "U10") (pin "7") (pinfunction "P$7_7") (pintype "output"))
      (node (ref "U11") (pin "3") (pinfunction "P$3_3") (pintype "input"))
    )
    (net (code "44") (name "COMMS_OFF") (class "Default")
      (node (ref "C87") (pin "1") (pinfunction "1_1") (pintype "passive"))
      (node (ref "R43") (pin "2") (pinfunction "2_2") (pintype "passive"))
      (node (ref "U12") (pin "3") (pinfunction "P$3_3") (pintype "input"))
      (node (ref "X1") (pin "25") (pinfunction "25_25") (pintype "bidirectional"))
    )
    (net (code "45") (name "COMMS_SCL") (class "Default")
      (node (ref "R30") (pin "1") (pinfunction "1_1") (pintype "passive"))
      (node (ref "R32") (pin "1") (pinfunction "1_1") (pintype "passive"))
      (node (ref "X1") (pin "41") (pinfunction "41_41") (pintype "bidirectional"))
      (node (ref "X3") (pin "2") (pinfunction "2_2") (pintype "passive"))
    )
    (net (code "46") (name "COMMS_SDA") (class "Default")
      (node (ref "R27") (pin "1") (pinfunction "1_1") (pintype "passive"))
      (node (ref "R31") (pin "1") (pinfunction "1_1") (pintype "passive"))
      (node (ref "X1") (pin "43") (pinfunction "43_43") (pintype "bidirectional"))
      (node (ref "X3") (pin "1") (pinfunction "1_1") (pintype "passive"))
    )
    (net (code "47") (name "GND") (class "Default")
      (node (ref "C1") (pin "2") (pinfunction "2_2") (pintype "passive"))
      (node (ref "C11") (pin "P$2") (pinfunction "2_P$2") (pintype "passive"))
      (node (ref "C12") (pin "2") (pinfunction "2_2") (pintype "passive"))
      (node (ref "C13") (pin "2") (pinfunction "2_2") (pintype "passive"))
      (node (ref "C14") (pin "2") (pinfunction "2_2") (pintype "passive"))
      (node (ref "C16") (pin "1") (pinfunction "1_1") (pintype "passive"))
      (node (ref "C17") (pin "1") (pinfunction "1_1") (pintype "passive"))
      (node (ref "C18") (pin "2") (pinfunction "2_2") (pintype "passive"))
      (node (ref "C19") (pin "2") (pinfunction "2_2") (pintype "passive"))
      (node (ref "C2") (pin "2") (pinfunction "2_2") (pintype "passive"))
      (node (ref "C20") (pin "2") (pinfunction "2_2") (pintype "passive"))
      (node (ref "C21") (pin "2") (pinfunction "2_2") (pintype "passive"))
      (node (ref "C22") (pin "2") (pinfunction "2_2") (pintype "passive"))
      (node (ref "C23") (pin "1") (pinfunction "1_1") (pintype "passive"))
      (node (ref "C27") (pin "2") (pinfunction "2_2") (pintype "passive"))
      (node (ref "C28") (pin "1") (pinfunction "1_1") (pintype "passive"))
      (node (ref "C29") (pin "2") (pinfunction "2_2") (pintype "passive"))
      (node (ref "C30") (pin "2") (pinfunction "2_2") (pintype "passive"))
      (node (ref "C31") (pin "2") (pinfunction "2_2") (pintype "passive"))
      (node (ref "C32") (pin "1") (pinfunction "1_1") (pintype "passive"))
      (node (ref "C33") (pin "2") (pinfunction "2_2") (pintype "passive"))
      (node (ref "C34") (pin "2") (pinfunction "2_2") (pintype "passive"))
      (node (ref "C35") (pin "2") (pinfunction "2_2") (pintype "passive"))
      (node (ref "C36") (pin "1") (pinfunction "1_1") (pintype "passive"))
      (node (ref "C37") (pin "P$2") (pinfunction "2_P$2") (pintype "passive"))
      (node (ref "C39") (pin "2") (pinfunction "2_2") (pintype "passive"))
      (node (ref "C40") (pin "2") (pinfunction "2_2") (pintype "passive"))
      (node (ref "C41") (pin "P$2") (pinfunction "2_P$2") (pintype "passive"))
      (node (ref "C42") (pin "P$2") (pinfunction "2_P$2") (pintype "passive"))
      (node (ref "C43") (pin "2") (pinfunction "2_2") (pintype "passive"))
      (node (ref "C44") (pin "2") (pinfunction "2_2") (pintype "passive"))
      (node (ref "C45") (pin "P$2") (pinfunction "2_P$2") (pintype "passive"))
      (node (ref "C46") (pin "P$2") (pinfunction "2_P$2") (pintype "passive"))
      (node (ref "C47") (pin "2") (pinfunction "2_2") (pintype "passive"))
      (node (ref "C48") (pin "2") (pinfunction "2_2") (pintype "passive"))
      (node (ref "C49") (pin "2") (pinfunction "2_2") (pintype "passive"))
      (node (ref "C5") (pin "2") (pinfunction "2_2") (pintype "passive"))
      (node (ref "C50") (pin "2") (pinfunction "2_2") (pintype "passive"))
      (node (ref "C51") (pin "2") (pinfunction "2_2") (pintype "passive"))
      (node (ref "C52") (pin "2") (pinfunction "2_2") (pintype "passive"))
      (node (ref "C53") (pin "2") (pinfunction "2_2") (pintype "passive"))
      (node (ref "C56") (pin "2") (pinfunction "2_2") (pintype "passive"))
      (node (ref "C57") (pin "2") (pinfunction "2_2") (pintype "passive"))
      (node (ref "C58") (pin "2") (pinfunction "2_2") (pintype "passive"))
      (node (ref "C59") (pin "2") (pinfunction "2_2") (pintype "passive"))
      (node (ref "C6") (pin "P$2") (pinfunction "2_P$2") (pintype "passive"))
      (node (ref "C60") (pin "2") (pinfunction "2_2") (pintype "passive"))
      (node (ref "C62") (pin "2") (pinfunction "2_2") (pintype "passive"))
      (node (ref "C63") (pin "2") (pinfunction "2_2") (pintype "passive"))
      (node (ref "C64") (pin "2") (pinfunction "2_2") (pintype "passive"))
      (node (ref "C65") (pin "2") (pinfunction "2_2") (pintype "passive"))
      (node (ref "C66") (pin "2") (pinfunction "2_2") (pintype "passive"))
      (node (ref "C67") (pin "2") (pinfunction "2_2") (pintype "passive"))
      (node (ref "C69") (pin "2") (pinfunction "2_2") (pintype "passive"))
      (node (ref "C7") (pin "2") (pinfunction "2_2") (pintype "passive"))
      (node (ref "C70") (pin "2") (pinfunction "2_2") (pintype "passive"))
      (node (ref "C72") (pin "2") (pinfunction "2_2") (pintype "passive"))
      (node (ref "C73") (pin "2") (pinfunction "2_2") (pintype "passive"))
      (node (ref "C74") (pin "2") (pinfunction "2_2") (pintype "passive"))
      (node (ref "C75") (pin "2") (pinfunction "2_2") (pintype "passive"))
      (node (ref "C76") (pin "2") (pinfunction "2_2") (pintype "passive"))
      (node (ref "C77") (pin "2") (pinfunction "2_2") (pintype "passive"))
      (node (ref "C79") (pin "2") (pinfunction "2_2") (pintype "passive"))
      (node (ref "C80") (pin "2") (pinfunction "2_2") (pintype "passive"))
      (node (ref "C81") (pin "2") (pinfunction "2_2") (pintype "passive"))
      (node (ref "C82") (pin "2") (pinfunction "2_2") (pintype "passive"))
      (node (ref "C83") (pin "2") (pinfunction "2_2") (pintype "passive"))
      (node (ref "C84") (pin "2") (pinfunction "2_2") (pintype "passive"))
      (node (ref "C85") (pin "2") (pinfunction "2_2") (pintype "passive"))
      (node (ref "C86") (pin "2") (pinfunction "2_2") (pintype "passive"))
      (node (ref "C87") (pin "2") (pinfunction "2_2") (pintype "passive"))
      (node (ref "C88") (pin "2") (pinfunction "2_2") (pintype "passive"))
      (node (ref "C89") (pin "2") (pinfunction "-_2") (pintype "passive"))
      (node (ref "C91") (pin "2") (pinfunction "2_2") (pintype "passive"))
      (node (ref "C92") (pin "P$2") (pinfunction "2_P$2") (pintype "passive"))
      (node (ref "C93") (pin "2") (pinfunction "2_2") (pintype "passive"))
      (node (ref "F1") (pin "2") (pinfunction "P$2_2") (pintype "power_in"))
      (node (ref "F1") (pin "4") (pinfunction "P$4_4") (pintype "power_in"))
      (node (ref "JP2") (pin "2") (pinfunction "2_2") (pintype "passive"))
      (node (ref "L2") (pin "2") (pinfunction "2_2") (pintype "passive"))
      (node (ref "L4") (pin "2") (pinfunction "2_2") (pintype "passive"))
      (node (ref "LED1") (pin "C") (pinfunction "C_C") (pintype "passive"))
      (node (ref "LED2") (pin "C") (pinfunction "C_C") (pintype "passive"))
      (node (ref "R1") (pin "1") (pinfunction "1_1") (pintype "passive"))
      (node (ref "R11") (pin "1") (pinfunction "1_1") (pintype "passive"))
      (node (ref "R13") (pin "2") (pinfunction "2_2") (pintype "passive"))
      (node (ref "R17") (pin "1") (pinfunction "1_1") (pintype "passive"))
      (node (ref "R18") (pin "2") (pinfunction "2_2") (pintype "passive"))
      (node (ref "R19") (pin "2") (pinfunction "2_2") (pintype "passive"))
      (node (ref "R22") (pin "1") (pinfunction "1_1") (pintype "passive"))
      (node (ref "R23") (pin "1") (pinfunction "1_1") (pintype "passive"))
      (node (ref "R24") (pin "1") (pinfunction "1_1") (pintype "passive"))
      (node (ref "R4") (pin "1") (pinfunction "1_1") (pintype "passive"))
      (node (ref "R41") (pin "2") (pinfunction "2_2") (pintype "passive"))
      (node (ref "R42") (pin "1") (pinfunction "1_1") (pintype "passive"))
      (node (ref "R43") (pin "1") (pinfunction "1_1") (pintype "passive"))
      (node (ref "R7") (pin "2") (pinfunction "2_2") (pintype "passive"))
      (node (ref "R8") (pin "2") (pinfunction "2_2") (pintype "passive"))
      (node (ref "TCXO1") (pin "1") (pinfunction "P$1_1") (pintype "bidirectional"))
      (node (ref "TCXO1") (pin "2") (pinfunction "P$2_2") (pintype "bidirectional"))
      (node (ref "TCXO2") (pin "1") (pinfunction "P$1_1") (pintype "bidirectional"))
      (node (ref "TCXO2") (pin "2") (pinfunction "P$2_2") (pintype "bidirectional"))
      (node (ref "TP1") (pin "TP") (pinfunction "TP_TP") (pintype "input"))
      (node (ref "TR1") (pin "2") (pinfunction "S_2") (pintype "bidirectional"))
      (node (ref "U1") (pin "2") (pinfunction "2_2") (pintype "power_in"))
      (node (ref "U1") (pin "3") (pinfunction "3_3") (pintype "power_in"))
      (node (ref "U1") (pin "5") (pinfunction "5_5") (pintype "power_in"))
      (node (ref "U10") (pin "2") (pinfunction "P$2_2") (pintype "power_in"))
      (node (ref "U11") (pin "1") (pinfunction "P$1_1") (pintype "bidirectional"))
      (node (ref "U11") (pin "2") (pinfunction "P$2_2") (pintype "power_in"))
      (node (ref "U12") (pin "4") (pinfunction "P$4_4") (pintype "power_in"))
      (node (ref "U13") (pin "1") (pinfunction "1_1") (pintype "power_in"))
      (node (ref "U2") (pin "2") (pinfunction "P$2_2") (pintype "bidirectional"))
      (node (ref "U3") (pin "2") (pinfunction "P$2_2") (pintype "bidirectional"))
      (node (ref "U3") (pin "4") (pinfunction "P$4_4") (pintype "bidirectional"))
      (node (ref "U3") (pin "TPAD") (pinfunction "P$17_TPAD") (pintype "bidirectional"))
      (node (ref "U4") (pin "2") (pinfunction "V-_2") (pintype "power_in"))
      (node (ref "U5") (pin "8") (pinfunction "P$8_8") (pintype "power_in"))
      (node (ref "U6") (pin "4") (pinfunction "P$4_4") (pintype "power_in"))
      (node (ref "U6") (pin "PAD") (pinfunction "P$8_PAD") (pintype "power_in"))
      (node (ref "U7") (pin "12") (pinfunction "P$12_12") (pintype "bidirectional"))
      (node (ref "U7") (pin "19") (pinfunction "P$19_19") (pintype "bidirectional"))
      (node (ref "U7") (pin "22") (pinfunction "P$22_22") (pintype "bidirectional"))
      (node (ref "U7") (pin "29") (pinfunction "P$29_29") (pintype "bidirectional"))
      (node (ref "U7") (pin "45") (pinfunction "P$45_45") (pintype "bidirectional"))
      (node (ref "U7") (pin "47") (pinfunction "P$47_47") (pintype "bidirectional"))
      (node (ref "U7") (pin "5") (pinfunction "P$5_5") (pintype "bidirectional"))
      (node (ref "U7") (pin "EXP") (pinfunction "P$49_EXP") (pintype "bidirectional"))
      (node (ref "U8") (pin "12") (pinfunction "P$12_12") (pintype "bidirectional"))
      (node (ref "U8") (pin "19") (pinfunction "P$19_19") (pintype "bidirectional"))
      (node (ref "U8") (pin "22") (pinfunction "P$22_22") (pintype "bidirectional"))
      (node (ref "U8") (pin "29") (pinfunction "P$29_29") (pintype "bidirectional"))
      (node (ref "U8") (pin "45") (pinfunction "P$45_45") (pintype "bidirectional"))
      (node (ref "U8") (pin "47") (pinfunction "P$47_47") (pintype "bidirectional"))
      (node (ref "U8") (pin "5") (pinfunction "P$5_5") (pintype "bidirectional"))
      (node (ref "U8") (pin "6") (pinfunction "P$6_6") (pintype "bidirectional"))
      (node (ref "U8") (pin "7") (pinfunction "P$7_7") (pintype "bidirectional"))
      (node (ref "U8") (pin "EXP") (pinfunction "P$49_EXP") (pintype "bidirectional"))
      (node (ref "U9") (pin "53") (pinfunction "53_53") (pintype "input"))
      (node (ref "U9") (pin "62") (pinfunction "62_62") (pintype "power_in"))
      (node (ref "U9") (pin "63") (pinfunction "63_63") (pintype "power_in"))
      (node (ref "X1") (pin "1") (pinfunction "1_1") (pintype "bidirectional"))
      (node (ref "X1") (pin "2") (pinfunction "2_2") (pintype "bidirectional"))
      (node (ref "X1") (pin "51") (pinfunction "51_51") (pintype "bidirectional"))
      (node (ref "X1") (pin "52") (pinfunction "52_52") (pintype "bidirectional"))
      (node (ref "X2") (pin "2") (pinfunction "2_2") (pintype "power_in"))
      (node (ref "X2") (pin "3") (pinfunction "3_3") (pintype "power_in"))
      (node (ref "X2") (pin "4") (pinfunction "4_4") (pintype "power_in"))
      (node (ref "X2") (pin "5") (pinfunction "5_5") (pintype "power_in"))
      (node (ref "X3") (pin "3") (pinfunction "3_3") (pintype "passive"))
      (node (ref "X5") (pin "1") (pinfunction "1_1") (pintype "bidirectional"))
      (node (ref "X7") (pin "9") (pinfunction "9_9") (pintype "bidirectional"))
    )
    (net (code "48") (name "LED1") (class "Default")
      (node (ref "R39") (pin "1") (pinfunction "1_1") (pintype "passive"))
      (node (ref "U9") (pin "50") (pinfunction "50_50") (pintype "bidirectional"))
    )
    (net (code "49") (name "LED_-FAULT") (class "Default")
      (node (ref "X1") (pin "28") (pinfunction "28_28") (pintype "bidirectional"))
    )
    (net (code "50") (name "LED_OFF") (class "Default")
      (node (ref "X1") (pin "23") (pinfunction "23_23") (pintype "bidirectional"))
    )
    (net (code "51") (name "LED_SCL") (class "Default")
      (node (ref "X1") (pin "33") (pinfunction "33_33") (pintype "bidirectional"))
    )
    (net (code "52") (name "LED_SDA") (class "Default")
      (node (ref "X1") (pin "35") (pinfunction "35_35") (pintype "bidirectional"))
    )
    (net (code "53") (name "Net-(C2-Pad1)") (class "Default")
      (node (ref "C2") (pin "1") (pinfunction "1_1") (pintype "passive"))
      (node (ref "C3") (pin "2") (pinfunction "2_2") (pintype "passive"))
      (node (ref "L3") (pin "1") (pinfunction "1_1") (pintype "passive"))
    )
    (net (code "54") (name "Net-(C4-Pad1)") (class "Default")
      (node (ref "C4") (pin "1") (pinfunction "1_1") (pintype "passive"))
      (node (ref "L2") (pin "1") (pinfunction "1_1") (pintype "passive"))
      (node (ref "L3") (pin "2") (pinfunction "2_2") (pintype "passive"))
    )
    (net (code "55") (name "Net-(C4-Pad2)") (class "Default")
      (node (ref "C4") (pin "2") (pinfunction "2_2") (pintype "passive"))
      (node (ref "U1") (pin "4") (pinfunction "4_4") (pintype "output"))
    )
    (net (code "56") (name "Net-(C8-Pad1)") (class "Default")
      (node (ref "C8") (pin "1") (pinfunction "1_1") (pintype "passive"))
      (node (ref "L5") (pin "2") (pinfunction "2_2") (pintype "passive"))
    )
    (net (code "57") (name "Net-(C9-Pad1)") (class "Default")
      (node (ref "C9") (pin "1") (pinfunction "1_1") (pintype "passive"))
      (node (ref "L4") (pin "1") (pinfunction "1_1") (pintype "passive"))
      (node (ref "L6") (pin "2") (pinfunction "2_2") (pintype "passive"))
    )
    (net (code "58") (name "Net-(C10-Pad1)") (class "Default")
      (node (ref "C10") (pin "1") (pinfunction "1_1") (pintype "passive"))
      (node (ref "X2") (pin "1") (pinfunction "1_1") (pintype "bidirectional"))
    )
    (net (code "59") (name "Net-(C15-Pad2)") (class "Default")
      (node (ref "C15") (pin "2") (pinfunction "2_2") (pintype "passive"))
      (node (ref "C16") (pin "2") (pinfunction "2_2") (pintype "passive"))
      (node (ref "L8") (pin "2") (pinfunction "2_2") (pintype "passive"))
    )
    (net (code "60") (name "Net-(C17-Pad2)") (class "Default")
      (node (ref "C17") (pin "2") (pinfunction "2_2") (pintype "passive"))
      (node (ref "L10") (pin "2") (pinfunction "2_2") (pintype "passive"))
      (node (ref "L8") (pin "1") (pinfunction "1_1") (pintype "passive"))
    )
    (net (code "61") (name "Net-(C18-Pad1)") (class "Default")
      (node (ref "C18") (pin "1") (pinfunction "1_1") (pintype "passive"))
      (node (ref "C24") (pin "2") (pinfunction "2_2") (pintype "passive"))
      (node (ref "L11") (pin "1") (pinfunction "1_1") (pintype "passive"))
    )
    (net (code "62") (name "Net-(C19-Pad1)") (class "Default")
      (node (ref "C19") (pin "1") (pinfunction "1_1") (pintype "passive"))
      (node (ref "L11") (pin "2") (pinfunction "2_2") (pintype "passive"))
      (node (ref "L12") (pin "1") (pinfunction "1_1") (pintype "passive"))
    )
    (net (code "63") (name "Net-(C20-Pad1)") (class "Default")
      (node (ref "C20") (pin "1") (pinfunction "1_1") (pintype "passive"))
      (node (ref "C25") (pin "1") (pinfunction "1_1") (pintype "passive"))
      (node (ref "L12") (pin "2") (pinfunction "2_2") (pintype "passive"))
      (node (ref "R4") (pin "2") (pinfunction "2_2") (pintype "passive"))
    )
    (net (code "64") (name "Net-(C21-Pad1)") (class "Default")
      (node (ref "C21") (pin "1") (pinfunction "1_1") (pintype "passive"))
      (node (ref "C22") (pin "1") (pinfunction "1_1") (pintype "passive"))
      (node (ref "C26") (pin "1") (pinfunction "1_1") (pintype "passive"))
      (node (ref "L13") (pin "2") (pinfunction "2_2") (pintype "passive"))
    )
    (net (code "65") (name "Net-(C23-Pad2)") (class "Default")
      (node (ref "C23") (pin "2") (pinfunction "2_2") (pintype "passive"))
      (node (ref "C26") (pin "2") (pinfunction "2_2") (pintype "passive"))
      (node (ref "L10") (pin "1") (pinfunction "1_1") (pintype "passive"))
    )
    (net (code "66") (name "Net-(C38-Pad2)") (class "Default")
      (node (ref "C38") (pin "2") (pinfunction "2_2") (pintype "passive"))
      (node (ref "R6") (pin "1") (pinfunction "1_1") (pintype "passive"))
    )
    (net (code "67") (name "Net-(C41-1)") (class "Default")
      (node (ref "C41") (pin "P$1") (pinfunction "1_P$1") (pintype "passive"))
      (node (ref "C42") (pin "P$1") (pinfunction "1_P$1") (pintype "passive"))
      (node (ref "U5") (pin "11") (pinfunction "P$11_11") (pintype "power_in"))
      (node (ref "U5") (pin "14") (pinfunction "P$14_14") (pintype "power_in"))
      (node (ref "U5") (pin "15") (pinfunction "P$15_15") (pintype "power_in"))
      (node (ref "U5") (pin "2") (pinfunction "P$2_2") (pintype "power_in"))
      (node (ref "U5") (pin "3") (pinfunction "P$3_3") (pintype "power_in"))
      (node (ref "U5") (pin "6") (pinfunction "P$6_6") (pintype "power_in"))
      (node (ref "U6") (pin "1") (pinfunction "P$1_1") (pintype "power_in"))
      (node (ref "U6") (pin "2") (pinfunction "P$2_2") (pintype "input"))
    )
    (net (code "68") (name "Net-(C54-Pad2)") (class "Default")
      (node (ref "C54") (pin "2") (pinfunction "2_2") (pintype "passive"))
      (node (ref "R17") (pin "2") (pinfunction "2_2") (pintype "passive"))
    )
    (net (code "69") (name "Net-(C58-Pad1)") (class "Default")
      (node (ref "C58") (pin "1") (pinfunction "1_1") (pintype "passive"))
      (node (ref "R21") (pin "1") (pinfunction "1_1") (pintype "passive"))
    )
    (net (code "70") (name "Net-(C68-Pad2)") (class "Default")
      (node (ref "C68") (pin "2") (pinfunction "2_2") (pintype "passive"))
      (node (ref "R23") (pin "2") (pinfunction "2_2") (pintype "passive"))
    )
    (net (code "71") (name "Net-(C73-Pad1)") (class "Default")
      (node (ref "C73") (pin "1") (pinfunction "1_1") (pintype "passive"))
      (node (ref "R26") (pin "1") (pinfunction "1_1") (pintype "passive"))
    )
    (net (code "72") (name "Net-(C80-Pad1)") (class "Default")
      (node (ref "C80") (pin "1") (pinfunction "1_1") (pintype "passive"))
      (node (ref "Q1") (pin "2") (pinfunction "2_2") (pintype "passive"))
      (node (ref "U9") (pin "9") (pinfunction "9_9") (pintype "bidirectional"))
    )
    (net (code "73") (name "Net-(C81-Pad1)") (class "Default")
      (node (ref "C81") (pin "1") (pinfunction "1_1") (pintype "passive"))
      (node (ref "Q1") (pin "1") (pinfunction "1_1") (pintype "passive"))
      (node (ref "U9") (pin "8") (pinfunction "8_8") (pintype "input"))
    )
    (net (code "74") (name "Net-(C82-Pad1)") (class "Default")
      (node (ref "C82") (pin "1") (pinfunction "1_1") (pintype "passive"))
      (node (ref "U9") (pin "7") (pinfunction "7_7") (pintype "output"))
    )
    (net (code "75") (name "Net-(C89-+)") (class "Default")
      (node (ref "C88") (pin "1") (pinfunction "1_1") (pintype "passive"))
      (node (ref "C89") (pin "1") (pinfunction "+_1") (pintype "passive"))
      (node (ref "U12") (pin "6") (pinfunction "P$6_6") (pintype "output"))
      (node (ref "U12") (pin "7") (pinfunction "P$7_7") (pintype "output"))
      (node (ref "U13") (pin "3") (pinfunction "3_3") (pintype "power_in"))
    )
    (net (code "76") (name "Net-(C90--)") (class "Default")
      (node (ref "C90") (pin "2") (pinfunction "-_2") (pintype "passive"))
      (node (ref "R41") (pin "1") (pinfunction "1_1") (pintype "passive"))
    )
    (net (code "77") (name "Net-(F1-P$1)") (class "Default")
      (node (ref "C5") (pin "1") (pinfunction "1_1") (pintype "passive"))
      (node (ref "F1") (pin "1") (pinfunction "P$1_1") (pintype "input"))
      (node (ref "L6") (pin "1") (pinfunction "1_1") (pintype "passive"))
    )
    (net (code "78") (name "Net-(F1-P$3)") (class "Default")
      (node (ref "C8") (pin "2") (pinfunction "2_2") (pintype "passive"))
      (node (ref "F1") (pin "3") (pinfunction "P$3_3") (pintype "output"))
    )
    (net (code "79") (name "Net-(JP2-Pad1)") (class "Default")
      (node (ref "JP2") (pin "1") (pinfunction "1_1") (pintype "passive"))
      (node (ref "LED2") (pin "A") (pinfunction "A_A") (pintype "passive"))
      (node (ref "R39") (pin "2") (pinfunction "2_2") (pintype "passive"))
    )
    (net (code "80") (name "Net-(L5-Pad1)") (class "Default")
      (node (ref "L5") (pin "1") (pinfunction "1_1") (pintype "passive"))
      (node (ref "U1") (pin "1") (pinfunction "1_1") (pintype "bidirectional"))
    )
    (net (code "81") (name "Net-(L7-2)") (class "Default")
      (node (ref "C14") (pin "1") (pinfunction "1_1") (pintype "passive"))
      (node (ref "L7") (pin "P$2") (pinfunction "2_P$2") (pintype "passive"))
      (node (ref "L9") (pin "1") (pinfunction "1_1") (pintype "passive"))
    )
    (net (code "82") (name "Net-(L15-1)") (class "Default")
      (node (ref "L13") (pin "1") (pinfunction "1_1") (pintype "passive"))
      (node (ref "L15") (pin "P$1") (pinfunction "1_P$1") (pintype "passive"))
      (node (ref "U3") (pin "10") (pinfunction "P$10_10") (pintype "bidirectional"))
      (node (ref "U3") (pin "11") (pinfunction "P$11_11") (pintype "bidirectional"))
      (node (ref "U3") (pin "12") (pinfunction "P$12_12") (pintype "bidirectional"))
      (node (ref "U3") (pin "9") (pinfunction "P$9_9") (pintype "bidirectional"))
    )
    (net (code "83") (name "Net-(LED1-PadA)") (class "Default")
      (node (ref "LED1") (pin "A") (pinfunction "A_A") (pintype "passive"))
      (node (ref "R38") (pin "2") (pinfunction "2_2") (pintype "passive"))
    )
    (net (code "84") (name "Net-(R27-Pad2)") (class "Default")
      (node (ref "R27") (pin "2") (pinfunction "2_2") (pintype "passive"))
      (node (ref "U9") (pin "29") (pinfunction "29_29") (pintype "bidirectional"))
    )
    (net (code "85") (name "Net-(R28-Pad1)") (class "Default")
      (node (ref "R28") (pin "1") (pinfunction "1_1") (pintype "passive"))
      (node (ref "U9") (pin "23") (pinfunction "23_23") (pintype "bidirectional"))
    )
    (net (code "86") (name "Net-(R29-Pad1)") (class "Default")
      (node (ref "R29") (pin "1") (pinfunction "1_1") (pintype "passive"))
      (node (ref "U9") (pin "24") (pinfunction "24_24") (pintype "bidirectional"))
    )
    (net (code "87") (name "Net-(R30-Pad2)") (class "Default")
      (node (ref "R30") (pin "2") (pinfunction "2_2") (pintype "passive"))
      (node (ref "U9") (pin "31") (pinfunction "31_31") (pintype "bidirectional"))
    )
    (net (code "88") (name "Net-(R34-Pad1)") (class "Default")
      (node (ref "R34") (pin "1") (pinfunction "1_1") (pintype "passive"))
      (node (ref "U9") (pin "15") (pinfunction "15_15") (pintype "bidirectional"))
    )
    (net (code "89") (name "Net-(R35-Pad1)") (class "Default")
      (node (ref "R35") (pin "1") (pinfunction "1_1") (pintype "passive"))
      (node (ref "U9") (pin "14") (pinfunction "14_14") (pintype "bidirectional"))
    )
    (net (code "90") (name "Net-(R38-Pad1)") (class "Default")
      (node (ref "R38") (pin "1") (pinfunction "1_1") (pintype "passive"))
      (node (ref "U9") (pin "49") (pinfunction "49_49") (pintype "bidirectional"))
    )
    (net (code "91") (name "Net-(R40-Pad1)") (class "Default")
      (node (ref "R40") (pin "1") (pinfunction "1_1") (pintype "passive"))
      (node (ref "X7") (pin "10") (pinfunction "10_10") (pintype "bidirectional"))
    )
    (net (code "92") (name "Net-(TCXO1-P$3)") (class "Default")
      (node (ref "C61") (pin "1") (pinfunction "1_1") (pintype "passive"))
      (node (ref "TCXO1") (pin "3") (pinfunction "P$3_3") (pintype "bidirectional"))
    )
    (net (code "93") (name "Net-(TCXO2-P$3)") (class "Default")
      (node (ref "C78") (pin "1") (pinfunction "1_1") (pintype "passive"))
      (node (ref "TCXO2") (pin "3") (pinfunction "P$3_3") (pintype "bidirectional"))
    )
    (net (code "94") (name "Net-(TR1-D)") (class "Default")
      (node (ref "C40") (pin "1") (pinfunction "1_1") (pintype "passive"))
      (node (ref "R15") (pin "1") (pinfunction "1_1") (pintype "passive"))
      (node (ref "TR1") (pin "3") (pinfunction "D_3") (pintype "bidirectional"))
      (node (ref "U5") (pin "7") (pinfunction "P$7_7") (pintype "input"))
    )
    (net (code "95") (name "Net-(TR1-G)") (class "Default")
      (node (ref "R10") (pin "1") (pinfunction "1_1") (pintype "passive"))
      (node (ref "TR1") (pin "1") (pinfunction "G_1") (pintype "bidirectional"))
    )
    (net (code "96") (name "Net-(U2-P$1)") (class "Default")
      (node (ref "C15") (pin "1") (pinfunction "1_1") (pintype "passive"))
      (node (ref "U2") (pin "1") (pinfunction "P$1_1") (pintype "bidirectional"))
    )
    (net (code "97") (name "Net-(U2-P$3)") (class "Default")
      (node (ref "C9") (pin "2") (pinfunction "2_2") (pintype "passive"))
      (node (ref "U2") (pin "3") (pinfunction "P$3_3") (pintype "bidirectional"))
    )
    (net (code "98") (name "Net-(U2-P$4)") (class "Default")
      (node (ref "R2") (pin "2") (pinfunction "2_2") (pintype "passive"))
      (node (ref "U2") (pin "4") (pinfunction "P$4_4") (pintype "bidirectional"))
    )
    (net (code "99") (name "Net-(U2-P$5)") (class "Default")
      (node (ref "C10") (pin "2") (pinfunction "2_2") (pintype "passive"))
      (node (ref "U2") (pin "5") (pinfunction "P$5_5") (pintype "bidirectional"))
    )
    (net (code "100") (name "Net-(U2-P$6)") (class "Default")
      (node (ref "R3") (pin "1") (pinfunction "1_1") (pintype "passive"))
      (node (ref "U2") (pin "6") (pinfunction "P$6_6") (pintype "bidirectional"))
    )
    (net (code "101") (name "Net-(U3-P$1)") (class "Default")
      (node (ref "R5") (pin "1") (pinfunction "1_1") (pintype "passive"))
      (node (ref "U3") (pin "1") (pinfunction "P$1_1") (pintype "bidirectional"))
    )
    (net (code "102") (name "Net-(U3-P$3)") (class "Default")
      (node (ref "C25") (pin "2") (pinfunction "2_2") (pintype "passive"))
      (node (ref "U3") (pin "3") (pinfunction "P$3_3") (pintype "bidirectional"))
    )
    (net (code "103") (name "Net-(U3-P$5)") (class "Default")
      (node (ref "L9") (pin "2") (pinfunction "2_2") (pintype "passive"))
      (node (ref "U3") (pin "5") (pinfunction "P$5_5") (pintype "bidirectional"))
      (node (ref "U3") (pin "6") (pinfunction "P$6_6") (pintype "bidirectional"))
    )
    (net (code "104") (name "Net-(U4-+IN)") (class "Default")
      (node (ref "C39") (pin "1") (pinfunction "1_1") (pintype "passive"))
      (node (ref "R14") (pin "2") (pinfunction "2_2") (pintype "passive"))
      (node (ref "U4") (pin "3") (pinfunction "+IN_3") (pintype "input"))
    )
    (net (code "105") (name "Net-(U4-OUT)") (class "Default")
      (node (ref "JP1") (pin "2") (pinfunction "2_2") (pintype "passive"))
      (node (ref "U4") (pin "1") (pinfunction "OUT_1") (pintype "output"))
    )
    (net (code "106") (name "Net-(U5-P$9)") (class "Default")
      (node (ref "R11") (pin "2") (pinfunction "2_2") (pintype "passive"))
      (node (ref "U5") (pin "9") (pinfunction "P$9_9") (pintype "passive"))
    )
    (net (code "107") (name "Net-(U6-P$3)") (class "Default")
      (node (ref "C43") (pin "1") (pinfunction "1_1") (pintype "passive"))
      (node (ref "U6") (pin "3") (pinfunction "P$3_3") (pintype "passive"))
    )
    (net (code "108") (name "Net-(U6-P$5)") (class "Default")
      (node (ref "R6") (pin "2") (pinfunction "2_2") (pintype "passive"))
      (node (ref "R8") (pin "1") (pinfunction "1_1") (pintype "passive"))
      (node (ref "R9") (pin "2") (pinfunction "2_2") (pintype "passive"))
      (node (ref "U6") (pin "5") (pinfunction "P$5_5") (pintype "input"))
    )
    (net (code "109") (name "Net-(U7-P$2)") (class "Default")
      (node (ref "C54") (pin "1") (pinfunction "1_1") (pintype "passive"))
      (node (ref "C55") (pin "2") (pinfunction "2_2") (pintype "passive"))
      (node (ref "U7") (pin "2") (pinfunction "P$2_2") (pintype "bidirectional"))
    )
    (net (code "110") (name "Net-(U7-P$8)") (class "Default")
      (node (ref "R19") (pin "1") (pinfunction "1_1") (pintype "passive"))
      (node (ref "U7") (pin "8") (pinfunction "P$8_8") (pintype "bidirectional"))
    )
    (net (code "111") (name "Net-(U7-P$10)") (class "Default")
      (node (ref "R18") (pin "1") (pinfunction "1_1") (pintype "passive"))
      (node (ref "U7") (pin "10") (pinfunction "P$10_10") (pintype "bidirectional"))
    )
    (net (code "112") (name "Net-(U7-P$11)") (class "Default")
      (node (ref "C49") (pin "1") (pinfunction "1_1") (pintype "passive"))
      (node (ref "U7") (pin "11") (pinfunction "P$11_11") (pintype "bidirectional"))
    )
    (net (code "113") (name "Net-(U7-P$31)") (class "Default")
      (node (ref "C50") (pin "1") (pinfunction "1_1") (pintype "passive"))
      (node (ref "U7") (pin "31") (pinfunction "P$31_31") (pintype "bidirectional"))
    )
    (net (code "114") (name "Net-(U7-P$41)") (class "Default")
      (node (ref "C60") (pin "1") (pinfunction "1_1") (pintype "passive"))
      (node (ref "U7") (pin "41") (pinfunction "P$41_41") (pintype "bidirectional"))
    )
    (net (code "115") (name "Net-(U7-P$48)") (class "Default")
      (node (ref "C55") (pin "1") (pinfunction "1_1") (pintype "passive"))
      (node (ref "U7") (pin "48") (pinfunction "P$48_48") (pintype "bidirectional"))
    )
    (net (code "116") (name "Net-(U8-P$2)") (class "Default")
      (node (ref "C68") (pin "1") (pinfunction "1_1") (pintype "passive"))
      (node (ref "C71") (pin "2") (pinfunction "2_2") (pintype "passive"))
      (node (ref "U8") (pin "2") (pinfunction "P$2_2") (pintype "bidirectional"))
    )
    (net (code "117") (name "Net-(U8-P$8)") (class "Default")
      (node (ref "R24") (pin "2") (pinfunction "2_2") (pintype "passive"))
      (node (ref "U8") (pin "8") (pinfunction "P$8_8") (pintype "bidirectional"))
    )
    (net (code "118") (name "Net-(U8-P$10)") (class "Default")
      (node (ref "R22") (pin "2") (pinfunction "2_2") (pintype "passive"))
      (node (ref "U8") (pin "10") (pinfunction "P$10_10") (pintype "bidirectional"))
    )
    (net (code "119") (name "Net-(U8-P$11)") (class "Default")
      (node (ref "C65") (pin "1") (pinfunction "1_1") (pintype "passive"))
      (node (ref "U8") (pin "11") (pinfunction "P$11_11") (pintype "bidirectional"))
    )
    (net (code "120") (name "Net-(U8-P$31)") (class "Default")
      (node (ref "C66") (pin "1") (pinfunction "1_1") (pintype "passive"))
      (node (ref "U8") (pin "31") (pinfunction "P$31_31") (pintype "bidirectional"))
    )
    (net (code "121") (name "Net-(U8-P$41)") (class "Default")
      (node (ref "C77") (pin "1") (pinfunction "1_1") (pintype "passive"))
      (node (ref "U8") (pin "41") (pinfunction "P$41_41") (pintype "bidirectional"))
    )
    (net (code "122") (name "Net-(U8-P$48)") (class "Default")
      (node (ref "C71") (pin "1") (pinfunction "1_1") (pintype "passive"))
      (node (ref "U8") (pin "48") (pinfunction "P$48_48") (pintype "bidirectional"))
    )
    (net (code "123") (name "Net-(U9-Pad34)") (class "Default")
      (node (ref "U9") (pin "34") (pinfunction "34_34") (pintype "bidirectional"))
      (node (ref "X5") (pin "2") (pinfunction "2_2") (pintype "bidirectional"))
    )
    (net (code "124") (name "Net-(U9-Pad35)") (class "Default")
      (node (ref "U9") (pin "35") (pinfunction "35_35") (pintype "bidirectional"))
      (node (ref "X5") (pin "3") (pinfunction "3_3") (pintype "bidirectional"))
    )
    (net (code "125") (name "Net-(U9-Pad54)") (class "Default")
      (node (ref "U9") (pin "54") (pinfunction "54_54") (pintype "bidirectional"))
      (node (ref "X7") (pin "1") (pinfunction "1_1") (pintype "bidirectional"))
    )
    (net (code "126") (name "Net-(U9-Pad55)") (class "Default")
      (node (ref "U9") (pin "55") (pinfunction "55_55") (pintype "input"))
      (node (ref "X7") (pin "3") (pinfunction "3_3") (pintype "bidirectional"))
    )
    (net (code "127") (name "Net-(U9-Pad56)") (class "Default")
      (node (ref "U9") (pin "56") (pinfunction "56_56") (pintype "input"))
      (node (ref "X7") (pin "5") (pinfunction "5_5") (pintype "bidirectional"))
    )
    (net (code "128") (name "Net-(U9-Pad57)") (class "Default")
      (node (ref "U9") (pin "57") (pinfunction "57_57") (pintype "input"))
      (node (ref "X7") (pin "7") (pinfunction "7_7") (pintype "bidirectional"))
    )
    (net (code "129") (name "Net-(U10-P$1)") (class "Default")
      (node (ref "U10") (pin "1") (pinfunction "P$1_1") (pintype "input"))
      (node (ref "U9") (pin "42") (pinfunction "42_42") (pintype "bidirectional"))
    )
    (net (code "130") (name "Net-(U12-P$5)") (class "Default")
      (node (ref "R42") (pin "2") (pinfunction "2_2") (pintype "passive"))
      (node (ref "U12") (pin "5") (pinfunction "P$5_5") (pintype "passive"))
    )
    (net (code "131") (name "Net-(X4-P$1)") (class "Default")
      (node (ref "U9") (pin "32") (pinfunction "32_32") (pintype "bidirectional"))
      (node (ref "X4") (pin "1") (pinfunction "P$1_1") (pintype "bidirectional"))
    )
    (net (code "132") (name "Net-(X6-P$1)") (class "Default")
      (node (ref "U9") (pin "33") (pinfunction "33_33") (pintype "bidirectional"))
      (node (ref "X6") (pin "1") (pinfunction "P$1_1") (pintype "bidirectional"))
    )
    (net (code "133") (name "OBC_-FAULT") (class "Default")
      (node (ref "R33") (pin "2") (pinfunction "2_2") (pintype "passive"))
      (node (ref "R36") (pin "1") (pinfunction "1_1") (pintype "passive"))
      (node (ref "X1") (pin "34") (pinfunction "34_34") (pintype "bidirectional"))
    )
    (net (code "134") (name "OBC_-FAULT_IN") (class "Default")
      (node (ref "R33") (pin "1") (pinfunction "1_1") (pintype "passive"))
      (node (ref "U9") (pin "12") (pinfunction "12_12") (pintype "bidirectional"))
    )
    (net (code "135") (name "OBC_OFF") (class "Default")
      (node (ref "R37") (pin "2") (pinfunction "2_2") (pintype "passive"))
      (node (ref "X1") (pin "26") (pinfunction "26_26") (pintype "bidirectional"))
    )
    (net (code "136") (name "OBC_OFF_OUT") (class "Default")
      (node (ref "R37") (pin "1") (pinfunction "1_1") (pintype "passive"))
      (node (ref "U9") (pin "2") (pinfunction "2_2") (pintype "bidirectional"))
    )
    (net (code "137") (name "PANELTEMP_SCL") (class "Default")
      (node (ref "X1") (pin "29") (pinfunction "29_29") (pintype "bidirectional"))
    )
    (net (code "138") (name "PANELTEMP_SDA") (class "Default")
      (node (ref "X1") (pin "31") (pinfunction "31_31") (pintype "bidirectional"))
    )
    (net (code "139") (name "PA_-FAULT") (class "Default")
      (node (ref "R12") (pin "2") (pinfunction "2_2") (pintype "passive"))
      (node (ref "U5") (pin "10") (pinfunction "P$10_10") (pintype "output"))
    )
    (net (code "140") (name "PA_BIAS") (class "Default")
      (node (ref "R13") (pin "1") (pinfunction "1_1") (pintype "passive"))
      (node (ref "R14") (pin "1") (pinfunction "1_1") (pintype "passive"))
      (node (ref "R16") (pin "2") (pinfunction "2_2") (pintype "passive"))
      (node (ref "U9") (pin "5") (pinfunction "5_5") (pintype "bidirectional"))
    )
    (net (code "141") (name "PA_ON") (class "Default")
      (node (ref "R10") (pin "2") (pinfunction "2_2") (pintype "passive"))
      (node (ref "R7") (pin "1") (pinfunction "1_1") (pintype "passive"))
      (node (ref "U9") (pin "40") (pinfunction "40_40") (pintype "input"))
    )
    (net (code "142") (name "RX_ON") (class "Default")
      (node (ref "U9") (pin "39") (pinfunction "39_39") (pintype "bidirectional"))
    )
    (net (code "143") (name "SCCHG_EN") (class "Default")
      (node (ref "X1") (pin "21") (pinfunction "21_21") (pintype "bidirectional"))
    )
    (net (code "144") (name "SCOUT_-PG") (class "Default")
      (node (ref "X1") (pin "50") (pinfunction "50_50") (pintype "bidirectional"))
    )
    (net (code "145") (name "SCOUT_EN") (class "Default")
      (node (ref "X1") (pin "22") (pinfunction "22_22") (pintype "bidirectional"))
    )
    (net (code "146") (name "SC_-ON") (class "Default")
      (node (ref "X1") (pin "40") (pinfunction "40_40") (pintype "bidirectional"))
    )
    (net (code "147") (name "SC_-PFO") (class "Default")
      (node (ref "X1") (pin "48") (pinfunction "48_48") (pintype "bidirectional"))
    )
    (net (code "148") (name "SOLAR_-ON") (class "Default")
      (node (ref "X1") (pin "36") (pinfunction "36_36") (pintype "bidirectional"))
    )
    (net (code "149") (name "SOLAR_CS1") (class "Default")
      (node (ref "X1") (pin "15") (pinfunction "15_15") (pintype "bidirectional"))
    )
    (net (code "150") (name "SOLAR_CS2") (class "Default")
      (node (ref "X1") (pin "14") (pinfunction "14_14") (pintype "bidirectional"))
    )
    (net (code "151") (name "SOLAR_CS3") (class "Default")
      (node (ref "X1") (pin "17") (pinfunction "17_17") (pintype "bidirectional"))
    )
    (net (code "152") (name "SOLAR_CS4") (class "Default")
      (node (ref "X1") (pin "16") (pinfunction "16_16") (pintype "bidirectional"))
    )
    (net (code "153") (name "SOLAR_CS5") (class "Default")
      (node (ref "X1") (pin "18") (pinfunction "18_18") (pintype "bidirectional"))
    )
    (net (code "154") (name "STRUT_GND") (class "Default")
      (node (ref "H4") (pin "B3,2") (pinfunction "MOUNT_B3,2") (pintype "passive"))
    )
    (net (code "155") (name "SUPERCAP_TEMP") (class "Default")
      (node (ref "X1") (pin "49") (pinfunction "49_49") (pintype "bidirectional"))
    )
    (net (code "156") (name "TX_ON") (class "Default")
      (node (ref "R1") (pin "2") (pinfunction "2_2") (pintype "passive"))
      (node (ref "R2") (pin "1") (pinfunction "1_1") (pintype "passive"))
      (node (ref "U9") (pin "38") (pinfunction "38_38") (pintype "bidirectional"))
    )
    (net (code "157") (name "VAPC") (class "Default")
      (node (ref "C28") (pin "2") (pinfunction "2_2") (pintype "passive"))
      (node (ref "C32") (pin "2") (pinfunction "2_2") (pintype "passive"))
      (node (ref "JP1") (pin "1") (pinfunction "1_1") (pintype "passive"))
      (node (ref "U3") (pin "15") (pinfunction "P$15_15") (pintype "bidirectional"))
      (node (ref "U3") (pin "16") (pinfunction "P$16_16") (pintype "bidirectional"))
    )
    (net (code "158") (name "VBAT") (class "Default")
      (node (ref "X1") (pin "11") (pinfunction "11_11") (pintype "bidirectional"))
      (node (ref "X1") (pin "12") (pinfunction "12_12") (pintype "bidirectional"))
    )
    (net (code "159") (name "VBUS") (class "Default")
      (node (ref "R15") (pin "2") (pinfunction "2_2") (pintype "passive"))
      (node (ref "U12") (pin "1") (pinfunction "P$1_1") (pintype "input"))
      (node (ref "U12") (pin "2") (pinfunction "P$2_2") (pintype "input"))
      (node (ref "U5") (pin "1") (pinfunction "P$1_1") (pintype "power_in"))
      (node (ref "U5") (pin "12") (pinfunction "P$12_12") (pintype "power_in"))
      (node (ref "U5") (pin "13") (pinfunction "P$13_13") (pintype "power_in"))
      (node (ref "U5") (pin "16") (pinfunction "P$16_16") (pintype "power_in"))
      (node (ref "U5") (pin "4") (pinfunction "P$4_4") (pintype "power_in"))
      (node (ref "U5") (pin "5") (pinfunction "P$5_5") (pintype "power_in"))
      (node (ref "X1") (pin "10") (pinfunction "10_10") (pintype "bidirectional"))
      (node (ref "X1") (pin "7") (pinfunction "7_7") (pintype "bidirectional"))
      (node (ref "X1") (pin "8") (pinfunction "8_8") (pintype "bidirectional"))
      (node (ref "X1") (pin "9") (pinfunction "9_9") (pintype "bidirectional"))
    )
    (net (code "160") (name "VCCRF") (class "Default")
      (node (ref "C29") (pin "1") (pinfunction "1_1") (pintype "passive"))
      (node (ref "C34") (pin "1") (pinfunction "1_1") (pintype "passive"))
      (node (ref "C48") (pin "1") (pinfunction "1_1") (pintype "passive"))
      (node (ref "C51") (pin "1") (pinfunction "1_1") (pintype "passive"))
      (node (ref "C52") (pin "1") (pinfunction "1_1") (pintype "passive"))
      (node (ref "C53") (pin "1") (pinfunction "1_1") (pintype "passive"))
      (node (ref "C56") (pin "1") (pinfunction "1_1") (pintype "passive"))
      (node (ref "C59") (pin "1") (pinfunction "1_1") (pintype "passive"))
      (node (ref "C6") (pin "P$1") (pinfunction "1_P$1") (pintype "passive"))
      (node (ref "C63") (pin "1") (pinfunction "1_1") (pintype "passive"))
      (node (ref "C64") (pin "1") (pinfunction "1_1") (pintype "passive"))
      (node (ref "C67") (pin "1") (pinfunction "1_1") (pintype "passive"))
      (node (ref "C69") (pin "1") (pinfunction "1_1") (pintype "passive"))
      (node (ref "C7") (pin "1") (pinfunction "1_1") (pintype "passive"))
      (node (ref "C70") (pin "1") (pinfunction "1_1") (pintype "passive"))
      (node (ref "C74") (pin "1") (pinfunction "1_1") (pintype "passive"))
      (node (ref "C76") (pin "1") (pinfunction "1_1") (pintype "passive"))
      (node (ref "C79") (pin "1") (pinfunction "1_1") (pintype "passive"))
      (node (ref "C93") (pin "1") (pinfunction "1_1") (pintype "passive"))
      (node (ref "L14") (pin "2") (pinfunction "2_2") (pintype "passive"))
      (node (ref "L16") (pin "2") (pinfunction "2_2") (pintype "passive"))
      (node (ref "R3") (pin "2") (pinfunction "2_2") (pintype "passive"))
      (node (ref "TCXO1") (pin "4") (pinfunction "P$4_4") (pintype "bidirectional"))
      (node (ref "TCXO2") (pin "4") (pinfunction "P$4_4") (pintype "bidirectional"))
      (node (ref "U1") (pin "6") (pinfunction "6_6") (pintype "power_in"))
      (node (ref "U7") (pin "3") (pinfunction "P$3_3") (pintype "bidirectional"))
      (node (ref "U7") (pin "32") (pinfunction "P$32_32") (pintype "bidirectional"))
      (node (ref "U7") (pin "40") (pinfunction "P$40_40") (pintype "bidirectional"))
      (node (ref "U7") (pin "43") (pinfunction "P$43_43") (pintype "bidirectional"))
      (node (ref "U7") (pin "9") (pinfunction "P$9_9") (pintype "bidirectional"))
      (node (ref "U8") (pin "3") (pinfunction "P$3_3") (pintype "bidirectional"))
      (node (ref "U8") (pin "32") (pinfunction "P$32_32") (pintype "bidirectional"))
      (node (ref "U8") (pin "40") (pinfunction "P$40_40") (pintype "bidirectional"))
      (node (ref "U8") (pin "43") (pinfunction "P$43_43") (pintype "bidirectional"))
      (node (ref "U8") (pin "9") (pinfunction "P$9_9") (pintype "bidirectional"))
    )
    (net (code "161") (name "VCOMMS_PA") (class "Default")
      (node (ref "C11") (pin "P$1") (pinfunction "1_P$1") (pintype "passive"))
      (node (ref "C12") (pin "1") (pinfunction "1_1") (pintype "passive"))
      (node (ref "C13") (pin "1") (pinfunction "1_1") (pintype "passive"))
      (node (ref "C27") (pin "1") (pinfunction "1_1") (pintype "passive"))
      (node (ref "C30") (pin "1") (pinfunction "1_1") (pintype "passive"))
      (node (ref "C31") (pin "1") (pinfunction "1_1") (pintype "passive"))
      (node (ref "C33") (pin "1") (pinfunction "1_1") (pintype "passive"))
      (node (ref "C35") (pin "1") (pinfunction "1_1") (pintype "passive"))
      (node (ref "C36") (pin "2") (pinfunction "2_2") (pintype "passive"))
      (node (ref "C37") (pin "P$1") (pinfunction "1_P$1") (pintype "passive"))
      (node (ref "C38") (pin "1") (pinfunction "1_1") (pintype "passive"))
      (node (ref "C44") (pin "1") (pinfunction "1_1") (pintype "passive"))
      (node (ref "C45") (pin "P$1") (pinfunction "1_P$1") (pintype "passive"))
      (node (ref "C46") (pin "P$1") (pinfunction "1_P$1") (pintype "passive"))
      (node (ref "C47") (pin "1") (pinfunction "1_1") (pintype "passive"))
      (node (ref "L15") (pin "P$2") (pinfunction "2_P$2") (pintype "passive"))
      (node (ref "L7") (pin "P$1") (pinfunction "1_P$1") (pintype "passive"))
      (node (ref "R16") (pin "1") (pinfunction "1_1") (pintype "passive"))
      (node (ref "R5") (pin "2") (pinfunction "2_2") (pintype "passive"))
      (node (ref "R9") (pin "1") (pinfunction "1_1") (pintype "passive"))
      (node (ref "U3") (pin "14") (pinfunction "P$14_14") (pintype "bidirectional"))
      (node (ref "U4") (pin "5") (pinfunction "V+_5") (pintype "power_in"))
      (node (ref "U6") (pin "6") (pinfunction "P$6_6") (pintype "power_in"))
      (node (ref "U6") (pin "7") (pinfunction "P$7_7") (pintype "power_in"))
    )
    (net (code "162") (name "VSOLAR") (class "Default")
      (node (ref "X1") (pin "3") (pinfunction "3_3") (pintype "bidirectional"))
      (node (ref "X1") (pin "4") (pinfunction "4_4") (pintype "bidirectional"))
      (node (ref "X1") (pin "5") (pinfunction "5_5") (pintype "bidirectional"))
      (node (ref "X1") (pin "6") (pinfunction "6_6") (pintype "bidirectional"))
    )
    (net (code "163") (name "VSUPERCAP") (class "Default")
      (node (ref "X1") (pin "13") (pinfunction "13_13") (pintype "bidirectional"))
    )
    (net (code "164") (name "unconnected-(H1-MOUNT-PadB3,2)") (class "Default")
      (node (ref "H1") (pin "B3,2") (pinfunction "MOUNT_B3,2") (pintype "passive"))
    )
    (net (code "165") (name "unconnected-(H2-MOUNT-PadB3,2)") (class "Default")
      (node (ref "H2") (pin "B3,2") (pinfunction "MOUNT_B3,2") (pintype "passive"))
    )
    (net (code "166") (name "unconnected-(H3-MOUNT-PadB3,2)") (class "Default")
      (node (ref "H3") (pin "B3,2") (pinfunction "MOUNT_B3,2") (pintype "passive"))
    )
    (net (code "167") (name "unconnected-(U3-P$7-Pad7)") (class "Default")
      (node (ref "U3") (pin "7") (pinfunction "P$7_7") (pintype "bidirectional"))
    )
    (net (code "168") (name "unconnected-(U3-P$8-Pad8)") (class "Default")
      (node (ref "U3") (pin "8") (pinfunction "P$8_8") (pintype "bidirectional"))
    )
    (net (code "169") (name "unconnected-(U3-P$13-Pad13)") (class "Default")
      (node (ref "U3") (pin "13") (pinfunction "P$13_13") (pintype "bidirectional"))
    )
    (net (code "170") (name "unconnected-(U4--IN-Pad4)") (class "Default")
      (node (ref "U4") (pin "4") (pinfunction "-IN_4") (pintype "input"))
    )
    (net (code "171") (name "unconnected-(U7-P$4-Pad4)") (class "Default")
      (node (ref "U7") (pin "4") (pinfunction "P$4_4") (pintype "bidirectional"))
    )
    (net (code "172") (name "unconnected-(U7-P$13-Pad13)") (class "Default")
      (node (ref "U7") (pin "13") (pinfunction "P$13_13") (pintype "bidirectional"))
    )
    (net (code "173") (name "unconnected-(U7-P$14-Pad14)") (class "Default")
      (node (ref "U7") (pin "14") (pinfunction "P$14_14") (pintype "bidirectional"))
    )
    (net (code "174") (name "unconnected-(U7-P$15-Pad15)") (class "Default")
      (node (ref "U7") (pin "15") (pinfunction "P$15_15") (pintype "bidirectional"))
    )
    (net (code "175") (name "unconnected-(U7-P$16-Pad16)") (class "Default")
      (node (ref "U7") (pin "16") (pinfunction "P$16_16") (pintype "bidirectional"))
    )
    (net (code "176") (name "unconnected-(U7-P$17-Pad17)") (class "Default")
      (node (ref "U7") (pin "17") (pinfunction "P$17_17") (pintype "bidirectional"))
    )
    (net (code "177") (name "unconnected-(U7-P$18-Pad18)") (class "Default")
      (node (ref "U7") (pin "18") (pinfunction "P$18_18") (pintype "bidirectional"))
    )
    (net (code "178") (name "unconnected-(U7-P$20-Pad20)") (class "Default")
      (node (ref "U7") (pin "20") (pinfunction "P$20_20") (pintype "bidirectional"))
    )
    (net (code "179") (name "unconnected-(U7-P$21-Pad21)") (class "Default")
      (node (ref "U7") (pin "21") (pinfunction "P$21_21") (pintype "bidirectional"))
    )
    (net (code "180") (name "unconnected-(U7-P$23-Pad23)") (class "Default")
      (node (ref "U7") (pin "23") (pinfunction "P$23_23") (pintype "bidirectional"))
    )
    (net (code "181") (name "unconnected-(U7-P$30-Pad30)") (class "Default")
      (node (ref "U7") (pin "30") (pinfunction "P$30_30") (pintype "bidirectional"))
    )
    (net (code "182") (name "unconnected-(U7-P$38-Pad38)") (class "Default")
      (node (ref "U7") (pin "38") (pinfunction "P$38_38") (pintype "bidirectional"))
    )
    (net (code "183") (name "unconnected-(U7-P$44-Pad44)") (class "Default")
      (node (ref "U7") (pin "44") (pinfunction "P$44_44") (pintype "bidirectional"))
    )
    (net (code "184") (name "unconnected-(U7-P$46-Pad46)") (class "Default")
      (node (ref "U7") (pin "46") (pinfunction "P$46_46") (pintype "bidirectional"))
    )
    (net (code "185") (name "unconnected-(U8-P$13-Pad13)") (class "Default")
      (node (ref "U8") (pin "13") (pinfunction "P$13_13") (pintype "bidirectional"))
    )
    (net (code "186") (name "unconnected-(U8-P$14-Pad14)") (class "Default")
      (node (ref "U8") (pin "14") (pinfunction "P$14_14") (pintype "bidirectional"))
    )
    (net (code "187") (name "unconnected-(U8-P$15-Pad15)") (class "Default")
      (node (ref "U8") (pin "15") (pinfunction "P$15_15") (pintype "bidirectional"))
    )
    (net (code "188") (name "unconnected-(U8-P$16-Pad16)") (class "Default")
      (node (ref "U8") (pin "16") (pinfunction "P$16_16") (pintype "bidirectional"))
    )
    (net (code "189") (name "unconnected-(U8-P$17-Pad17)") (class "Default")
      (node (ref "U8") (pin "17") (pinfunction "P$17_17") (pintype "bidirectional"))
    )
    (net (code "190") (name "unconnected-(U8-P$18-Pad18)") (class "Default")
      (node (ref "U8") (pin "18") (pinfunction "P$18_18") (pintype "bidirectional"))
    )
    (net (code "191") (name "unconnected-(U8-P$20-Pad20)") (class "Default")
      (node (ref "U8") (pin "20") (pinfunction "P$20_20") (pintype "bidirectional"))
    )
    (net (code "192") (name "unconnected-(U8-P$21-Pad21)") (class "Default")
      (node (ref "U8") (pin "21") (pinfunction "P$21_21") (pintype "bidirectional"))
    )
    (net (code "193") (name "unconnected-(U8-P$23-Pad23)") (class "Default")
      (node (ref "U8") (pin "23") (pinfunction "P$23_23") (pintype "bidirectional"))
    )
    (net (code "194") (name "unconnected-(U8-P$30-Pad30)") (class "Default")
      (node (ref "U8") (pin "30") (pinfunction "P$30_30") (pintype "bidirectional"))
    )
    (net (code "195") (name "unconnected-(U8-P$33-Pad33)") (class "Default")
      (node (ref "U8") (pin "33") (pinfunction "P$33_33") (pintype "bidirectional"))
    )
    (net (code "196") (name "unconnected-(U8-P$38-Pad38)") (class "Default")
      (node (ref "U8") (pin "38") (pinfunction "P$38_38") (pintype "bidirectional"))
    )
    (net (code "197") (name "unconnected-(U8-P$44-Pad44)") (class "Default")
      (node (ref "U8") (pin "44") (pinfunction "P$44_44") (pintype "bidirectional"))
    )
    (net (code "198") (name "unconnected-(U8-P$46-Pad46)") (class "Default")
      (node (ref "U8") (pin "46") (pinfunction "P$46_46") (pintype "bidirectional"))
    )
    (net (code "199") (name "unconnected-(U9-Pad3)") (class "Default")
      (node (ref "U9") (pin "3") (pinfunction "3_3") (pintype "bidirectional"))
    )
    (net (code "200") (name "unconnected-(U9-Pad4)") (class "Default")
      (node (ref "U9") (pin "4") (pinfunction "4_4") (pintype "bidirectional"))
    )
    (net (code "201") (name "unconnected-(U9-Pad6)") (class "Default")
      (node (ref "U9") (pin "6") (pinfunction "6_6") (pintype "bidirectional"))
    )
    (net (code "202") (name "unconnected-(U9-Pad10)") (class "Default")
      (node (ref "U9") (pin "10") (pinfunction "10_10") (pintype "input"))
    )
    (net (code "203") (name "unconnected-(U9-Pad11)") (class "Default")
      (node (ref "U9") (pin "11") (pinfunction "11_11") (pintype "bidirectional"))
    )
    (net (code "204") (name "unconnected-(U9-Pad28)") (class "Default")
      (node (ref "U9") (pin "28") (pinfunction "28_28") (pintype "bidirectional"))
    )
    (net (code "205") (name "unconnected-(U9-Pad30)") (class "Default")
      (node (ref "U9") (pin "30") (pinfunction "30_30") (pintype "bidirectional"))
    )
    (net (code "206") (name "unconnected-(U9-Pad41)") (class "Default")
      (node (ref "U9") (pin "41") (pinfunction "41_41") (pintype "bidirectional"))
    )
    (net (code "207") (name "unconnected-(U9-Pad43)") (class "Default")
      (node (ref "U9") (pin "43") (pinfunction "43_43") (pintype "bidirectional"))
    )
    (net (code "208") (name "unconnected-(U9-Pad44)") (class "Default")
      (node (ref "U9") (pin "44") (pinfunction "44_44") (pintype "bidirectional"))
    )
    (net (code "209") (name "unconnected-(U9-Pad45)") (class "Default")
      (node (ref "U9") (pin "45") (pinfunction "45_45") (pintype "bidirectional"))
    )
    (net (code "210") (name "unconnected-(U9-Pad46)") (class "Default")
      (node (ref "U9") (pin "46") (pinfunction "46_46") (pintype "bidirectional"))
    )
    (net (code "211") (name "unconnected-(U9-Pad47)") (class "Default")
      (node (ref "U9") (pin "47") (pinfunction "47_47") (pintype "bidirectional"))
    )
    (net (code "212") (name "unconnected-(U9-Pad48)") (class "Default")
      (node (ref "U9") (pin "48") (pinfunction "48_48") (pintype "bidirectional"))
    )
    (net (code "213") (name "unconnected-(U9-Pad51)") (class "Default")
      (node (ref "U9") (pin "51") (pinfunction "51_51") (pintype "bidirectional"))
    )
    (net (code "214") (name "unconnected-(U9-Pad52)") (class "Default")
      (node (ref "U9") (pin "52") (pinfunction "52_52") (pintype "output"))
    )
    (net (code "215") (name "unconnected-(U9-Pad59)") (class "Default")
      (node (ref "U9") (pin "59") (pinfunction "59_59") (pintype "bidirectional"))
    )
    (net (code "216") (name "unconnected-(U9-Pad60)") (class "Default")
      (node (ref "U9") (pin "60") (pinfunction "60_60") (pintype "bidirectional"))
    )
    (net (code "217") (name "unconnected-(U9-Pad61)") (class "Default")
      (node (ref "U9") (pin "61") (pinfunction "61_61") (pintype "bidirectional"))
    )
    (net (code "218") (name "unconnected-(U10-P$3-Pad3)") (class "Default")
      (node (ref "U10") (pin "3") (pinfunction "P$3_3") (pintype "no_connect"))
    )
    (net (code "219") (name "unconnected-(X7-Pad2)") (class "Default")
      (node (ref "X7") (pin "2") (pinfunction "2_2") (pintype "bidirectional"))
    )
    (net (code "220") (name "unconnected-(X7-Pad6)") (class "Default")
      (node (ref "X7") (pin "6") (pinfunction "6_6") (pintype "bidirectional"))
    )
    (net (code "221") (name "unconnected-(X7-Pad8)") (class "Default")
      (node (ref "X7") (pin "8") (pinfunction "8_8") (pintype "bidirectional"))
    )
    (net (code "222") (name "{slash}RST") (class "Default")
      (node (ref "R40") (pin "2") (pinfunction "2_2") (pintype "passive"))
      (node (ref "R44") (pin "1") (pinfunction "1_1") (pintype "passive"))
      (node (ref "U11") (pin "4") (pinfunction "P$4_4") (pintype "output"))
      (node (ref "U9") (pin "58") (pinfunction "58_58") (pintype "input"))
    )
  )
)
